# SCH-CAPE-Nucleo_Interface_V1R0.net
KiCad netlist of a schematic drawn in Altium Designer
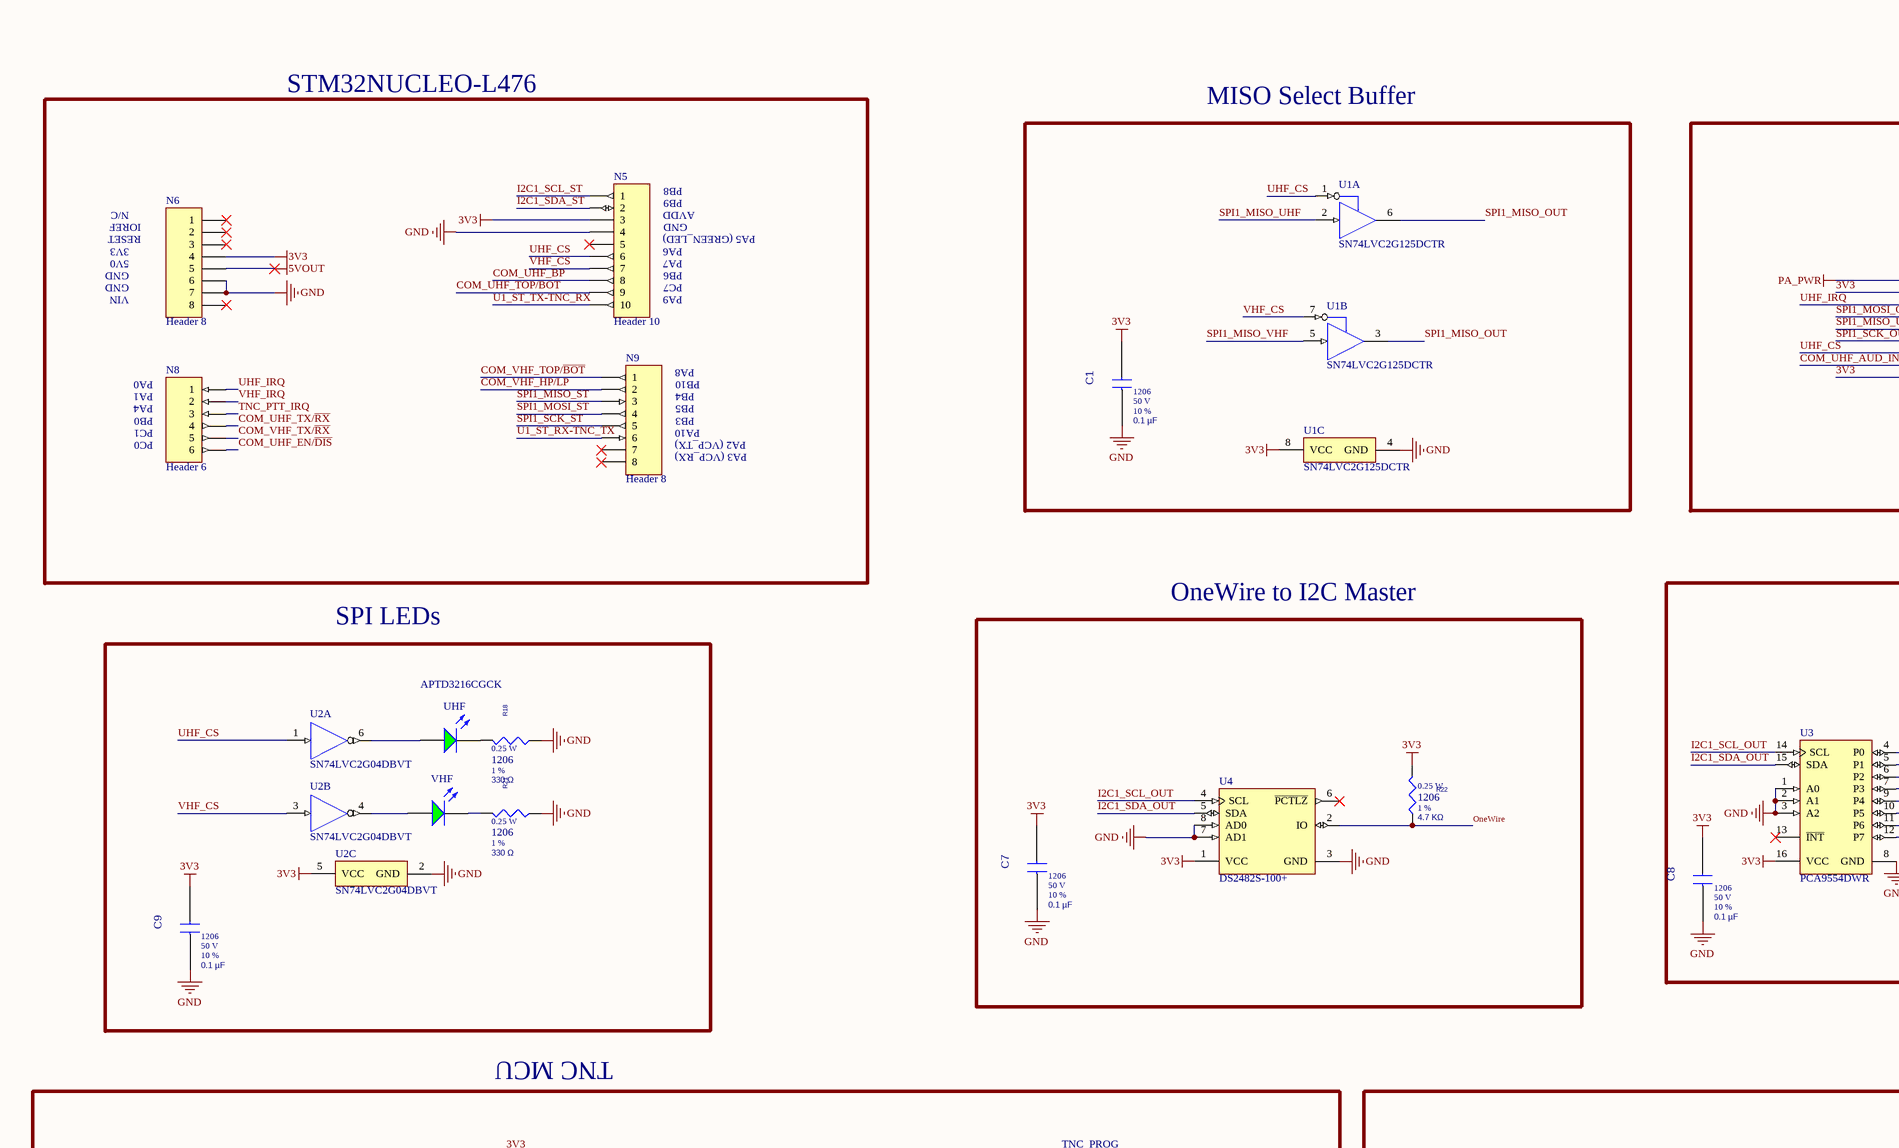
[diagram p0: SCH-CAPE-Nucleo_Interface_V1R0.SchDoc, top left]
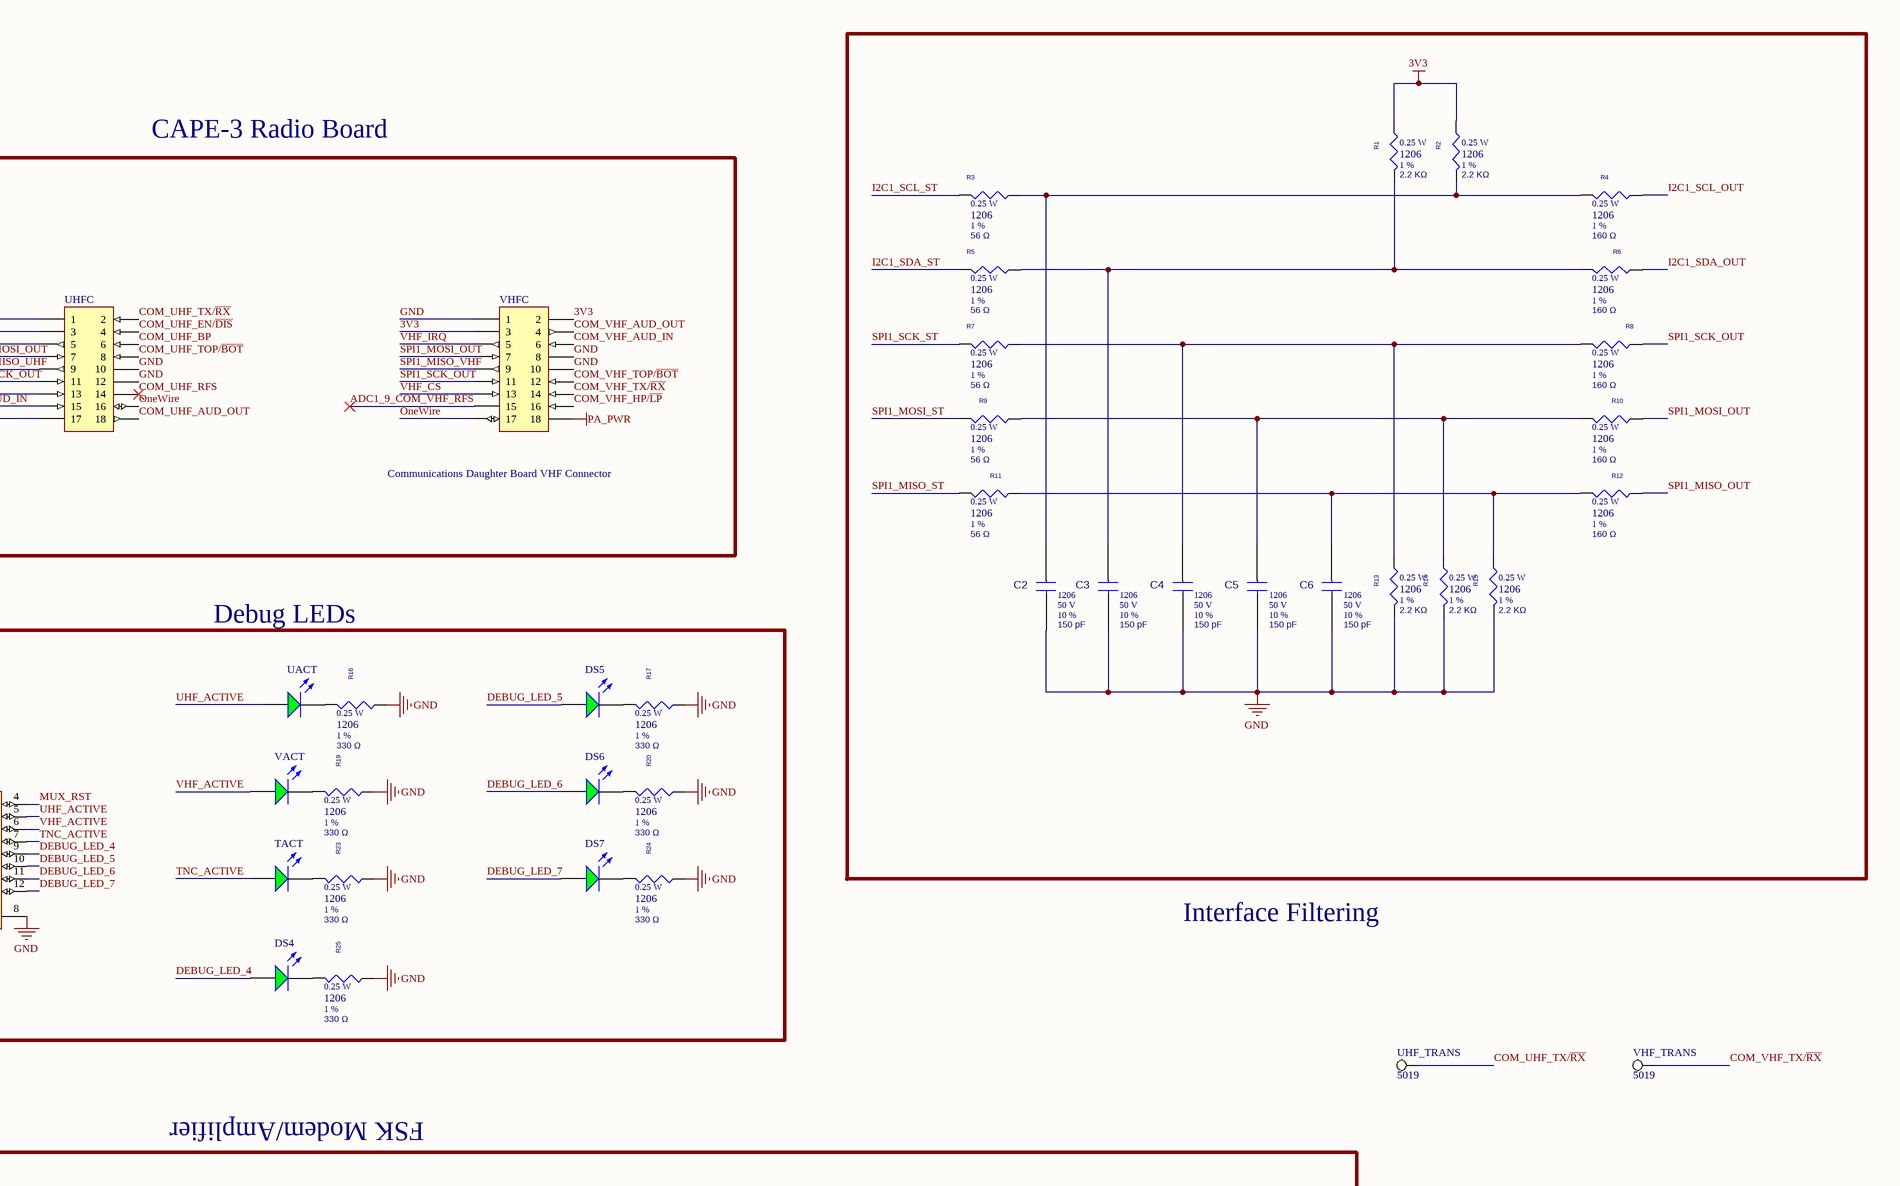
[diagram p1: SCH-CAPE-Nucleo_Interface_V1R0.SchDoc, top right]
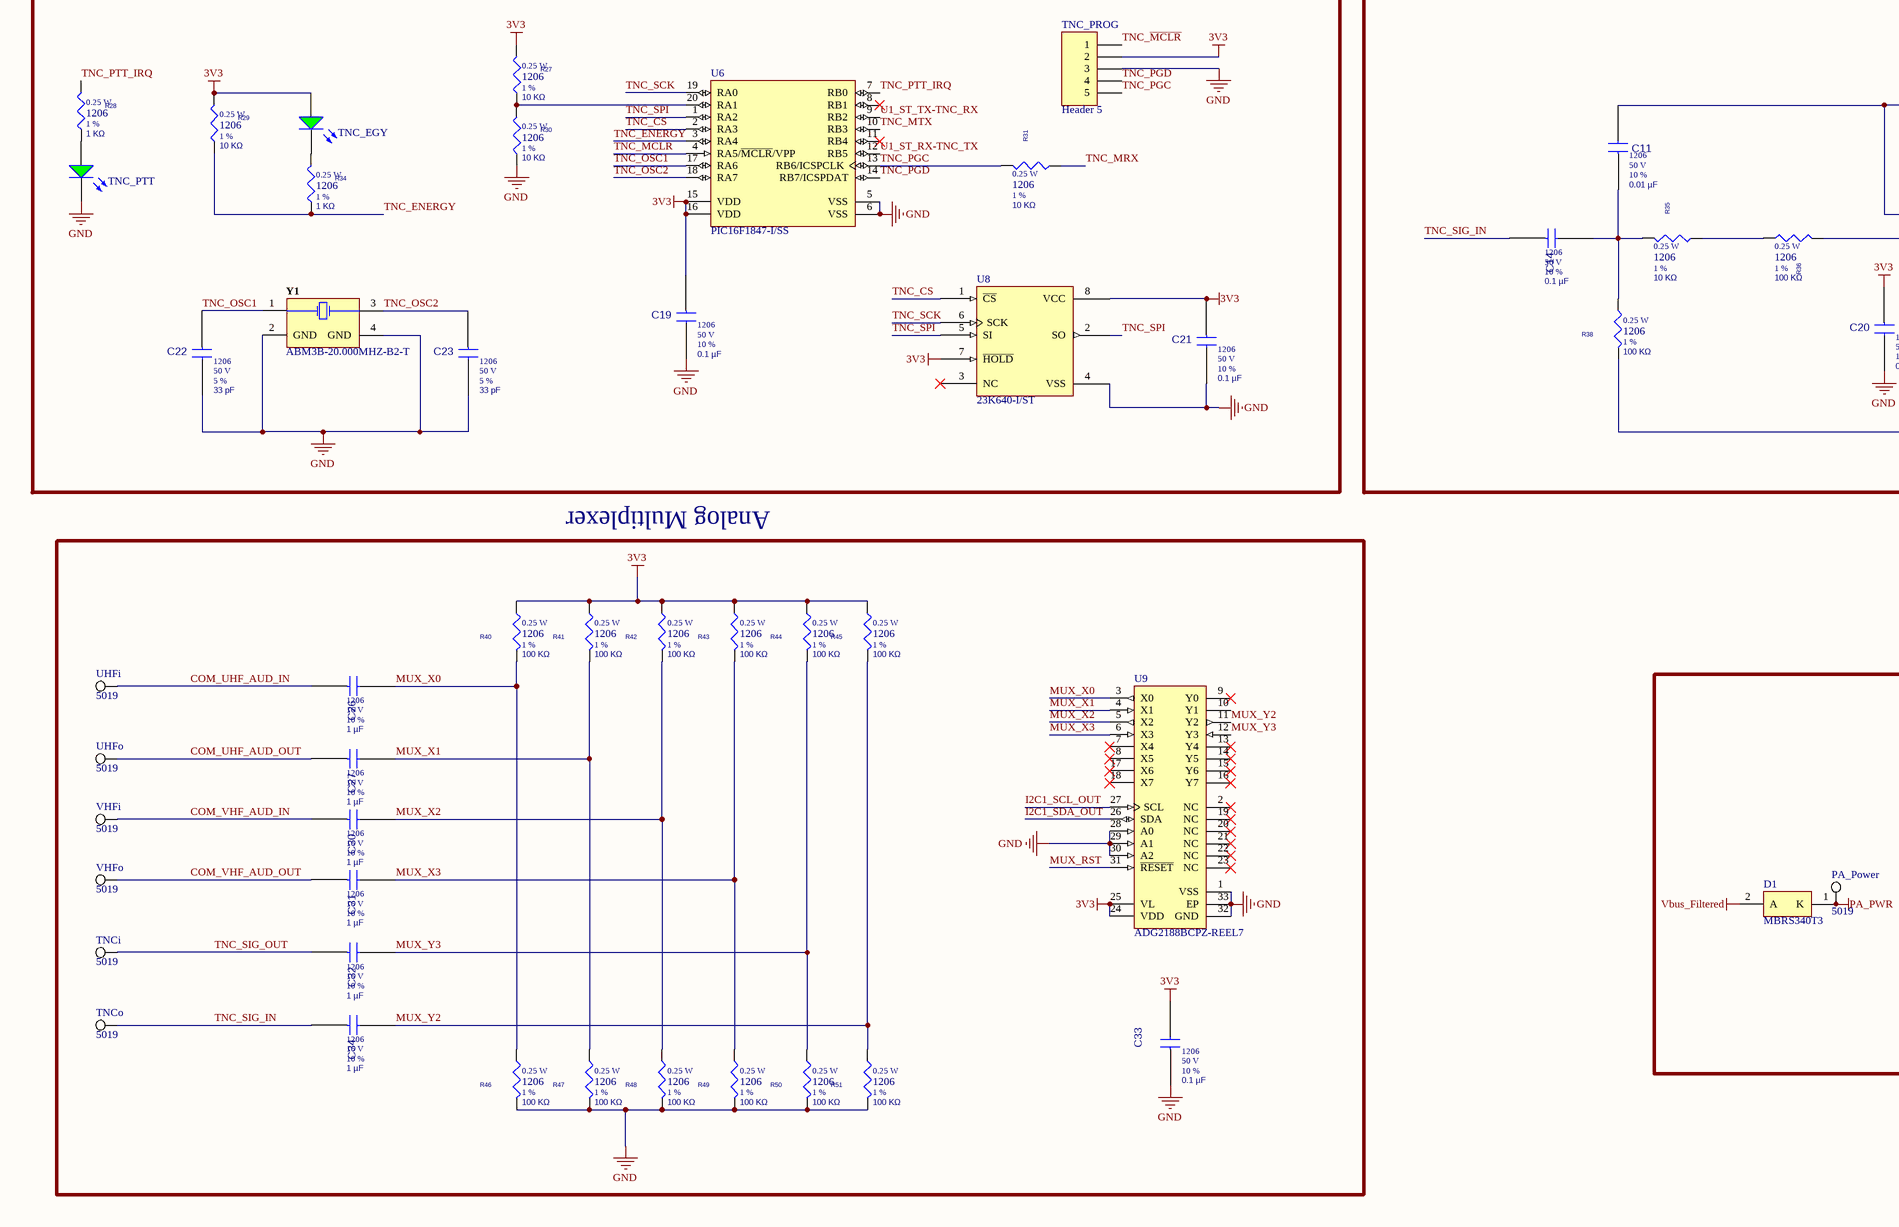
[diagram p2: SCH-CAPE-Nucleo_Interface_V1R0.SchDoc, bottom left]
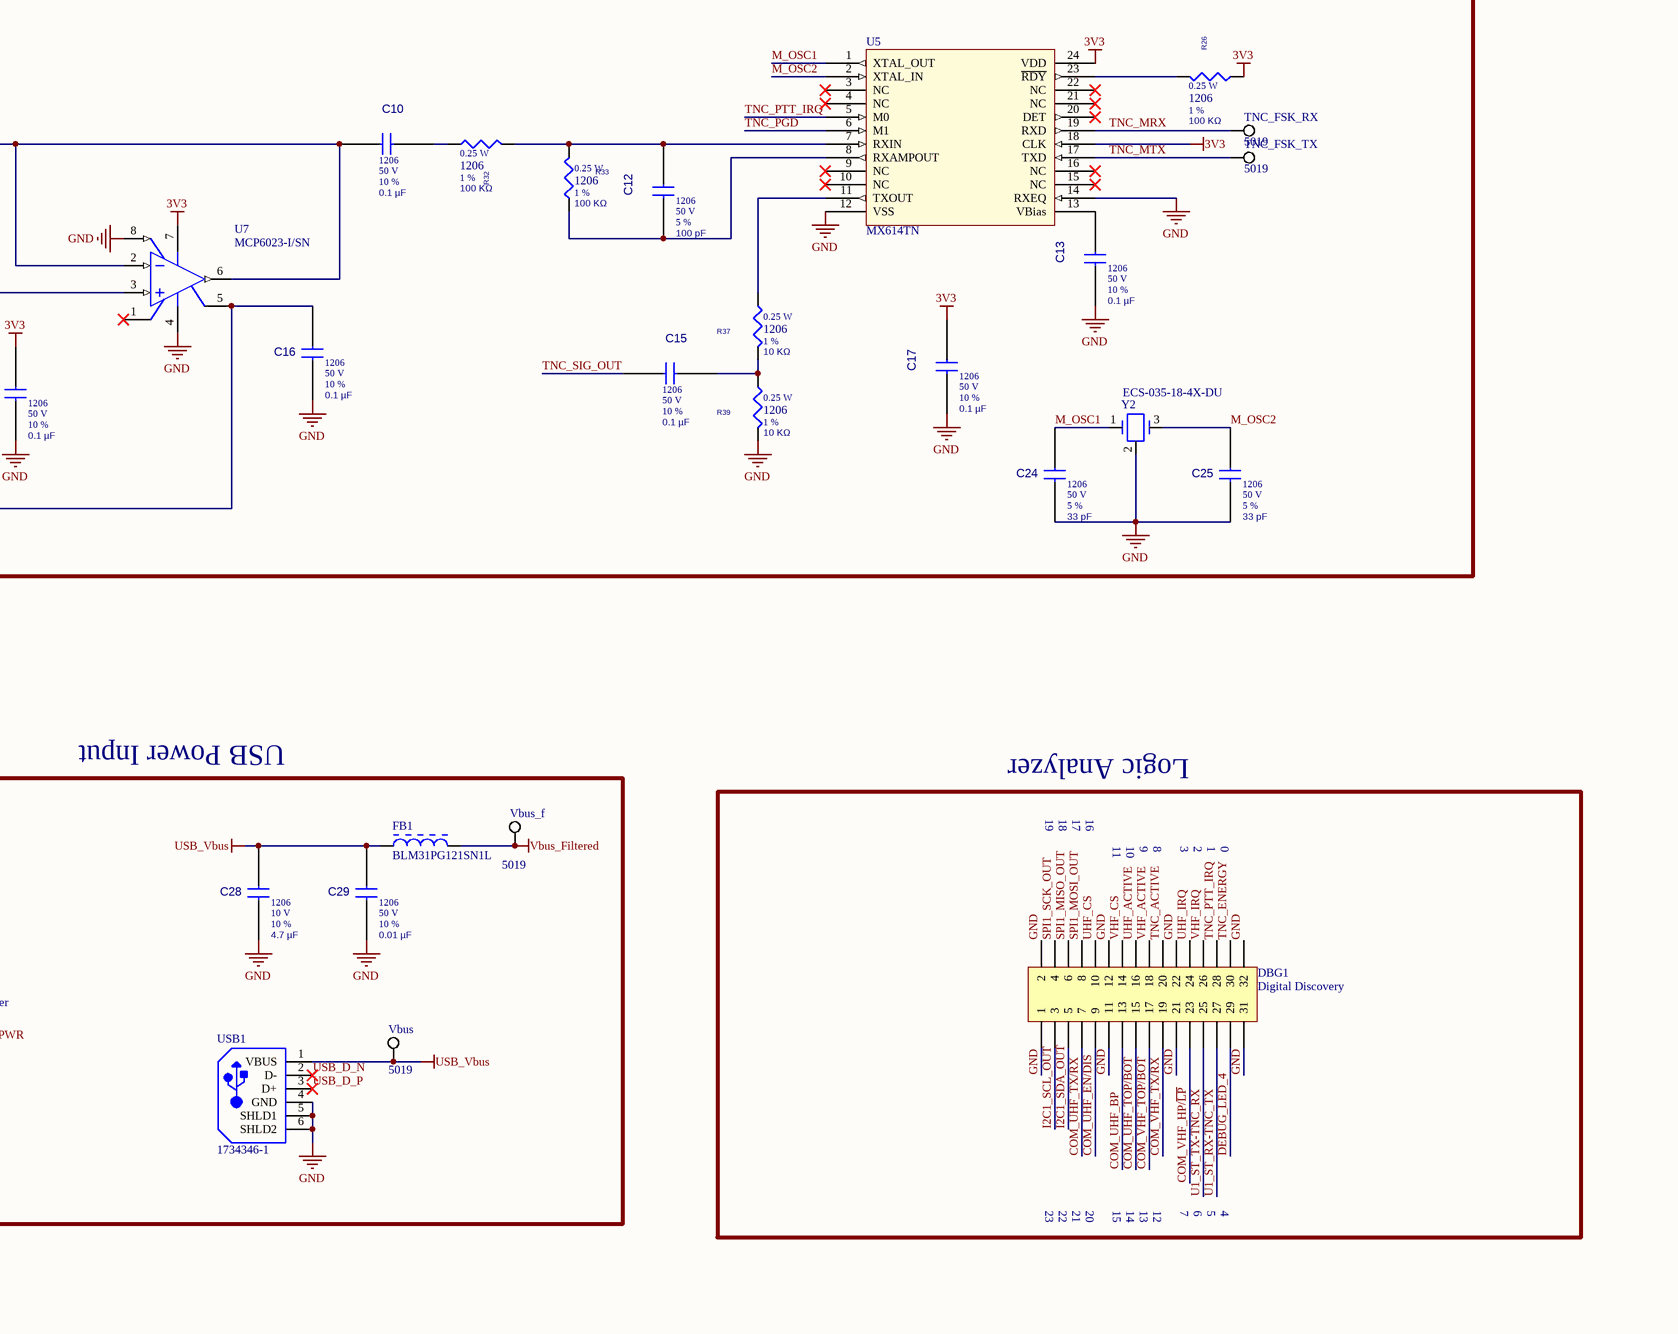
[diagram p3: SCH-CAPE-Nucleo_Interface_V1R0.SchDoc, bottom right]

(export (version "E")
  (design (tool "Eeschema 10.0.6"))
  (components
    (comp (ref "C1")
      (value "0.1 µF")
      (footprint "1206_GENERIC")
      (description "Ceramic Capacitor, =Value, =Tolerance, =VoltageRating, =Package")
      (fields
        (field (name "PART NUMBER") "CL31B104KBCNNNC")
        (field (name "MANUFACTURER") "Samsung")
        (field (name "PACKAGE") "1206")
        (field (name "VOLTAGE RATING") "50 V")
        (field (name "TOLERANCE") "10 %")
      )
      (libsource (lib "PEF") (part "SMT Capacitor"))
    )
    (comp (ref "C2")
      (value "150 pF")
      (footprint "1206_GENERIC")
      (description "Ceramic Capacitor, =Value, =Tolerance, =VoltageRating, =Package")
      (fields
        (field (name "PART NUMBER") "885012208101")
        (field (name "MANUFACTURER") "Wurth Electronics Inc.")
        (field (name "PACKAGE") "1206")
        (field (name "VOLTAGE RATING") "50 V")
        (field (name "TOLERANCE") "10 %")
      )
      (libsource (lib "PEF") (part "SMT Capacitor"))
    )
    (comp (ref "C3")
      (value "150 pF")
      (footprint "1206_GENERIC")
      (description "Ceramic Capacitor, =Value, =Tolerance, =VoltageRating, =Package")
      (fields
        (field (name "PART NUMBER") "885012208101")
        (field (name "MANUFACTURER") "Wurth Electronics Inc.")
        (field (name "PACKAGE") "1206")
        (field (name "VOLTAGE RATING") "50 V")
        (field (name "TOLERANCE") "10 %")
      )
      (libsource (lib "PEF") (part "SMT Capacitor"))
    )
    (comp (ref "C4")
      (value "150 pF")
      (footprint "1206_GENERIC")
      (description "Ceramic Capacitor, =Value, =Tolerance, =VoltageRating, =Package")
      (fields
        (field (name "PART NUMBER") "885012208101")
        (field (name "MANUFACTURER") "Wurth Electronics Inc.")
        (field (name "PACKAGE") "1206")
        (field (name "VOLTAGE RATING") "50 V")
        (field (name "TOLERANCE") "10 %")
      )
      (libsource (lib "PEF") (part "SMT Capacitor"))
    )
    (comp (ref "C5")
      (value "150 pF")
      (footprint "1206_GENERIC")
      (description "Ceramic Capacitor, =Value, =Tolerance, =VoltageRating, =Package")
      (fields
        (field (name "PART NUMBER") "885012208101")
        (field (name "MANUFACTURER") "Wurth Electronics Inc.")
        (field (name "PACKAGE") "1206")
        (field (name "VOLTAGE RATING") "50 V")
        (field (name "TOLERANCE") "10 %")
      )
      (libsource (lib "PEF") (part "SMT Capacitor"))
    )
    (comp (ref "C6")
      (value "150 pF")
      (footprint "1206_GENERIC")
      (description "Ceramic Capacitor, =Value, =Tolerance, =VoltageRating, =Package")
      (fields
        (field (name "PART NUMBER") "885012208101")
        (field (name "MANUFACTURER") "Wurth Electronics Inc.")
        (field (name "PACKAGE") "1206")
        (field (name "VOLTAGE RATING") "50 V")
        (field (name "TOLERANCE") "10 %")
      )
      (libsource (lib "PEF") (part "SMT Capacitor"))
    )
    (comp (ref "C7")
      (value "0.1 µF")
      (footprint "1206_GENERIC")
      (description "Ceramic Capacitor, =Value, =Tolerance, =VoltageRating, =Package")
      (fields
        (field (name "PART NUMBER") "CL31B104KBCNNNC")
        (field (name "MANUFACTURER") "Samsung")
        (field (name "PACKAGE") "1206")
        (field (name "VOLTAGE RATING") "50 V")
        (field (name "TOLERANCE") "10 %")
      )
      (libsource (lib "PEF") (part "SMT Capacitor"))
    )
    (comp (ref "C8")
      (value "0.1 µF")
      (footprint "1206_GENERIC")
      (description "Ceramic Capacitor, =Value, =Tolerance, =VoltageRating, =Package")
      (fields
        (field (name "PART NUMBER") "CL31B104KBCNNNC")
        (field (name "MANUFACTURER") "Samsung")
        (field (name "PACKAGE") "1206")
        (field (name "VOLTAGE RATING") "50 V")
        (field (name "TOLERANCE") "10 %")
      )
      (libsource (lib "PEF") (part "SMT Capacitor"))
    )
    (comp (ref "C9")
      (value "0.1 µF")
      (footprint "1206_GENERIC")
      (description "Ceramic Capacitor, =Value, =Tolerance, =VoltageRating, =Package")
      (fields
        (field (name "PART NUMBER") "CL31B104KBCNNNC")
        (field (name "MANUFACTURER") "Samsung")
        (field (name "PACKAGE") "1206")
        (field (name "VOLTAGE RATING") "50 V")
        (field (name "TOLERANCE") "10 %")
      )
      (libsource (lib "PEF") (part "SMT Capacitor"))
    )
    (comp (ref "C10")
      (value "0.1 µF")
      (footprint "1206_GENERIC")
      (description "Ceramic Capacitor, =Value, =Tolerance, =VoltageRating, =Package")
      (fields
        (field (name "PART NUMBER") "CL31B104KBCNNNC")
        (field (name "MANUFACTURER") "Samsung")
        (field (name "PACKAGE") "1206")
        (field (name "VOLTAGE RATING") "50 V")
        (field (name "TOLERANCE") "10 %")
      )
      (libsource (lib "PEF") (part "SMT Capacitor"))
    )
    (comp (ref "C11")
      (value "0.01 µF")
      (footprint "1206_GENERIC")
      (description "Ceramic Capacitor, =Value, =Tolerance, =VoltageRating, =Package")
      (fields
        (field (name "PART NUMBER") "CL31B103KBCNNNC")
        (field (name "MANUFACTURER") "Samsung")
        (field (name "PACKAGE") "1206")
        (field (name "VOLTAGE RATING") "50 V")
        (field (name "TOLERANCE") "10 %")
      )
      (libsource (lib "PEF") (part "SMT Capacitor"))
    )
    (comp (ref "C12")
      (value "100 pF")
      (footprint "1206_GENERIC")
      (description "Ceramic Capacitor, =Value, =Tolerance, =VoltageRating, =Package")
      (fields
        (field (name "PART NUMBER") "CL31C101JBCNNNC")
        (field (name "MANUFACTURER") "Samsung")
        (field (name "PACKAGE") "1206")
        (field (name "VOLTAGE RATING") "50 V")
        (field (name "TOLERANCE") "5 %")
      )
      (libsource (lib "PEF") (part "SMT Capacitor"))
    )
    (comp (ref "C13")
      (value "0.1 µF")
      (footprint "1206_GENERIC")
      (description "Ceramic Capacitor, =Value, =Tolerance, =VoltageRating, =Package")
      (fields
        (field (name "PART NUMBER") "CL31B104KBCNNNC")
        (field (name "MANUFACTURER") "Samsung")
        (field (name "PACKAGE") "1206")
        (field (name "VOLTAGE RATING") "50 V")
        (field (name "TOLERANCE") "10 %")
      )
      (libsource (lib "PEF") (part "SMT Capacitor"))
    )
    (comp (ref "C14")
      (value "0.1 µF")
      (footprint "1206_GENERIC")
      (description "Ceramic Capacitor, =Value, =Tolerance, =VoltageRating, =Package")
      (fields
        (field (name "PART NUMBER") "CL31B104KBCNNNC")
        (field (name "MANUFACTURER") "Samsung")
        (field (name "PACKAGE") "1206")
        (field (name "VOLTAGE RATING") "50 V")
        (field (name "TOLERANCE") "10 %")
      )
      (libsource (lib "PEF") (part "SMT Capacitor"))
    )
    (comp (ref "C15")
      (value "0.1 µF")
      (footprint "1206_GENERIC")
      (description "Ceramic Capacitor, =Value, =Tolerance, =VoltageRating, =Package")
      (fields
        (field (name "PART NUMBER") "CL31B104KBCNNNC")
        (field (name "MANUFACTURER") "Samsung")
        (field (name "PACKAGE") "1206")
        (field (name "VOLTAGE RATING") "50 V")
        (field (name "TOLERANCE") "10 %")
      )
      (libsource (lib "PEF") (part "SMT Capacitor"))
    )
    (comp (ref "C16")
      (value "0.1 µF")
      (footprint "1206_GENERIC")
      (description "Ceramic Capacitor, =Value, =Tolerance, =VoltageRating, =Package")
      (fields
        (field (name "PART NUMBER") "CL31B104KBCNNNC")
        (field (name "MANUFACTURER") "Samsung")
        (field (name "PACKAGE") "1206")
        (field (name "VOLTAGE RATING") "50 V")
        (field (name "TOLERANCE") "10 %")
      )
      (libsource (lib "PEF") (part "SMT Capacitor"))
    )
    (comp (ref "C17")
      (value "0.1 µF")
      (footprint "1206_GENERIC")
      (description "Ceramic Capacitor, =Value, =Tolerance, =VoltageRating, =Package")
      (fields
        (field (name "PART NUMBER") "CL31B104KBCNNNC")
        (field (name "MANUFACTURER") "Samsung")
        (field (name "PACKAGE") "1206")
        (field (name "VOLTAGE RATING") "50 V")
        (field (name "TOLERANCE") "10 %")
      )
      (libsource (lib "PEF") (part "SMT Capacitor"))
    )
    (comp (ref "C19")
      (value "0.1 µF")
      (footprint "1206_GENERIC")
      (description "Ceramic Capacitor, =Value, =Tolerance, =VoltageRating, =Package")
      (fields
        (field (name "PART NUMBER") "CL31B104KBCNNNC")
        (field (name "MANUFACTURER") "Samsung")
        (field (name "PACKAGE") "1206")
        (field (name "VOLTAGE RATING") "50 V")
        (field (name "TOLERANCE") "10 %")
      )
      (libsource (lib "PEF") (part "SMT Capacitor"))
    )
    (comp (ref "C20")
      (value "0.1 µF")
      (footprint "1206_GENERIC")
      (description "Ceramic Capacitor, =Value, =Tolerance, =VoltageRating, =Package")
      (fields
        (field (name "PART NUMBER") "CL31B104KBCNNNC")
        (field (name "MANUFACTURER") "Samsung")
        (field (name "PACKAGE") "1206")
        (field (name "VOLTAGE RATING") "50 V")
        (field (name "TOLERANCE") "10 %")
      )
      (libsource (lib "PEF") (part "SMT Capacitor"))
    )
    (comp (ref "C21")
      (value "0.1 µF")
      (footprint "1206_GENERIC")
      (description "Ceramic Capacitor, =Value, =Tolerance, =VoltageRating, =Package")
      (fields
        (field (name "PART NUMBER") "CL31B104KBCNNNC")
        (field (name "MANUFACTURER") "Samsung")
        (field (name "PACKAGE") "1206")
        (field (name "VOLTAGE RATING") "50 V")
        (field (name "TOLERANCE") "10 %")
      )
      (libsource (lib "PEF") (part "SMT Capacitor"))
    )
    (comp (ref "C22")
      (value "33 pF")
      (footprint "1206_GENERIC")
      (description "Ceramic Capacitor, =Value, =Tolerance, =VoltageRating, =Package")
      (fields
        (field (name "PART NUMBER") "CL31C330JBCNNNC")
        (field (name "MANUFACTURER") "Samsung")
        (field (name "PACKAGE") "1206")
        (field (name "VOLTAGE RATING") "50 V")
        (field (name "TOLERANCE") "5 %")
      )
      (libsource (lib "PEF") (part "SMT Capacitor"))
    )
    (comp (ref "C23")
      (value "33 pF")
      (footprint "1206_GENERIC")
      (description "Ceramic Capacitor, =Value, =Tolerance, =VoltageRating, =Package")
      (fields
        (field (name "PART NUMBER") "CL31C330JBCNNNC")
        (field (name "MANUFACTURER") "Samsung")
        (field (name "PACKAGE") "1206")
        (field (name "VOLTAGE RATING") "50 V")
        (field (name "TOLERANCE") "5 %")
      )
      (libsource (lib "PEF") (part "SMT Capacitor"))
    )
    (comp (ref "C24")
      (value "33 pF")
      (footprint "1206_GENERIC")
      (description "Ceramic Capacitor, =Value, =Tolerance, =VoltageRating, =Package")
      (fields
        (field (name "PART NUMBER") "CL31C330JBCNNNC")
        (field (name "MANUFACTURER") "Samsung")
        (field (name "PACKAGE") "1206")
        (field (name "VOLTAGE RATING") "50 V")
        (field (name "TOLERANCE") "5 %")
      )
      (libsource (lib "PEF") (part "SMT Capacitor"))
    )
    (comp (ref "C25")
      (value "33 pF")
      (footprint "1206_GENERIC")
      (description "Ceramic Capacitor, =Value, =Tolerance, =VoltageRating, =Package")
      (fields
        (field (name "PART NUMBER") "CL31C330JBCNNNC")
        (field (name "MANUFACTURER") "Samsung")
        (field (name "PACKAGE") "1206")
        (field (name "VOLTAGE RATING") "50 V")
        (field (name "TOLERANCE") "5 %")
      )
      (libsource (lib "PEF") (part "SMT Capacitor"))
    )
    (comp (ref "C26")
      (value "1 µF")
      (footprint "1206_GENERIC")
      (description "Ceramic Capacitor, =Value, =Tolerance, =VoltageRating, =Package")
      (fields
        (field (name "PART NUMBER") "CL31B105KOFNNNE")
        (field (name "MANUFACTURER") "Samsung")
        (field (name "PACKAGE") "1206")
        (field (name "VOLTAGE RATING") "16 V")
        (field (name "TOLERANCE") "10 %")
      )
      (libsource (lib "PEF") (part "SMT Capacitor"))
    )
    (comp (ref "C27")
      (value "1 µF")
      (footprint "1206_GENERIC")
      (description "Ceramic Capacitor, =Value, =Tolerance, =VoltageRating, =Package")
      (fields
        (field (name "PART NUMBER") "CL31B105KOFNNNE")
        (field (name "MANUFACTURER") "Samsung")
        (field (name "PACKAGE") "1206")
        (field (name "VOLTAGE RATING") "16 V")
        (field (name "TOLERANCE") "10 %")
      )
      (libsource (lib "PEF") (part "SMT Capacitor"))
    )
    (comp (ref "C28")
      (value "4.7 µF")
      (footprint "1206_GENERIC")
      (description "Ceramic Capacitor, =Value, =Tolerance, =VoltageRating, =Package")
      (fields
        (field (name "PART NUMBER") "CL31A475KPHNNNE")
        (field (name "MANUFACTURER") "Samsung")
        (field (name "PACKAGE") "1206")
        (field (name "VOLTAGE RATING") "10 V")
        (field (name "TOLERANCE") "10 %")
      )
      (libsource (lib "PEF") (part "SMT Capacitor"))
    )
    (comp (ref "C29")
      (value "0.01 µF")
      (footprint "1206_GENERIC")
      (description "Ceramic Capacitor, =Value, =Tolerance, =VoltageRating, =Package")
      (fields
        (field (name "PART NUMBER") "CL31B103KBCNNNC")
        (field (name "MANUFACTURER") "Samsung")
        (field (name "PACKAGE") "1206")
        (field (name "VOLTAGE RATING") "50 V")
        (field (name "TOLERANCE") "10 %")
      )
      (libsource (lib "PEF") (part "SMT Capacitor"))
    )
    (comp (ref "C30")
      (value "1 µF")
      (footprint "1206_GENERIC")
      (description "Ceramic Capacitor, =Value, =Tolerance, =VoltageRating, =Package")
      (fields
        (field (name "PART NUMBER") "CL31B105KOFNNNE")
        (field (name "MANUFACTURER") "Samsung")
        (field (name "PACKAGE") "1206")
        (field (name "VOLTAGE RATING") "16 V")
        (field (name "TOLERANCE") "10 %")
      )
      (libsource (lib "PEF") (part "SMT Capacitor"))
    )
    (comp (ref "C31")
      (value "1 µF")
      (footprint "1206_GENERIC")
      (description "Ceramic Capacitor, =Value, =Tolerance, =VoltageRating, =Package")
      (fields
        (field (name "PART NUMBER") "CL31B105KOFNNNE")
        (field (name "MANUFACTURER") "Samsung")
        (field (name "PACKAGE") "1206")
        (field (name "VOLTAGE RATING") "16 V")
        (field (name "TOLERANCE") "10 %")
      )
      (libsource (lib "PEF") (part "SMT Capacitor"))
    )
    (comp (ref "C32")
      (value "1 µF")
      (footprint "1206_GENERIC")
      (description "Ceramic Capacitor, =Value, =Tolerance, =VoltageRating, =Package")
      (fields
        (field (name "PART NUMBER") "CL31B105KOFNNNE")
        (field (name "MANUFACTURER") "Samsung")
        (field (name "PACKAGE") "1206")
        (field (name "VOLTAGE RATING") "16 V")
        (field (name "TOLERANCE") "10 %")
      )
      (libsource (lib "PEF") (part "SMT Capacitor"))
    )
    (comp (ref "C33")
      (value "0.1 µF")
      (footprint "1206_GENERIC")
      (description "Ceramic Capacitor, =Value, =Tolerance, =VoltageRating, =Package")
      (fields
        (field (name "PART NUMBER") "CL31B104KBCNNNC")
        (field (name "MANUFACTURER") "Samsung")
        (field (name "PACKAGE") "1206")
        (field (name "VOLTAGE RATING") "50 V")
        (field (name "TOLERANCE") "10 %")
      )
      (libsource (lib "PEF") (part "SMT Capacitor"))
    )
    (comp (ref "C34")
      (value "1 µF")
      (footprint "1206_GENERIC")
      (description "Ceramic Capacitor, =Value, =Tolerance, =VoltageRating, =Package")
      (fields
        (field (name "PART NUMBER") "CL31B105KOFNNNE")
        (field (name "MANUFACTURER") "Samsung")
        (field (name "PACKAGE") "1206")
        (field (name "VOLTAGE RATING") "16 V")
        (field (name "TOLERANCE") "10 %")
      )
      (libsource (lib "PEF") (part "SMT Capacitor"))
    )
    (comp (ref "D1")
      (value "MBRS340T3")
      (footprint "ONSC-SMC-2-403-03_V")
      (description "Schottky Power Rectifier, 2-Pin SMC, Tape and Reel")
      (fields (field (name "MANUFACTURER") "On Semiconductor"))
      (libsource (lib "Altium Content Vault") (part "ONSC-D-K1A2-2_A"))
    )
    (comp (ref "DBG1")
      (value "Digital Discovery")
      (footprint "HDR2X16H")
      (description "Header, 16-Pin, Dual row, Right Angle")
      (fields
        (field (name "PART NUMBER") "SSQ-116-02-T-D-RA")
        (field (name "MANUFACTURER") "Samtec")
        (field (name "PUBLISHER") "Altium Limited")
      )
      (libsource (lib "Miscellaneous Connectors") (part "Header 16X2H"))
    )
    (comp (ref "DS4")
      (value "APTD3216CGCK")
      (footprint "KING-APTD3216CGCK_V")
      (description "Chip LED Lamp, Green, 5 V, 30 mA, -40 to 85 degC, 2-Pin SMD, RoHS, Tape and Reel")
      (fields (field (name "MANUFACTURER") "Kingbright"))
      (libsource (lib "Altium Content Vault") (part "LED-GREEN-AK-2"))
    )
    (comp (ref "DS5")
      (value "APTD3216CGCK")
      (footprint "KING-APTD3216CGCK_V")
      (description "Chip LED Lamp, Green, 5 V, 30 mA, -40 to 85 degC, 2-Pin SMD, RoHS, Tape and Reel")
      (fields (field (name "MANUFACTURER") "Kingbright"))
      (libsource (lib "Altium Content Vault") (part "LED-GREEN-AK-2"))
    )
    (comp (ref "DS6")
      (value "APTD3216CGCK")
      (footprint "KING-APTD3216CGCK_V")
      (description "Chip LED Lamp, Green, 5 V, 30 mA, -40 to 85 degC, 2-Pin SMD, RoHS, Tape and Reel")
      (fields (field (name "MANUFACTURER") "Kingbright"))
      (libsource (lib "Altium Content Vault") (part "LED-GREEN-AK-2"))
    )
    (comp (ref "DS7")
      (value "APTD3216CGCK")
      (footprint "KING-APTD3216CGCK_V")
      (description "Chip LED Lamp, Green, 5 V, 30 mA, -40 to 85 degC, 2-Pin SMD, RoHS, Tape and Reel")
      (fields (field (name "MANUFACTURER") "Kingbright"))
      (libsource (lib "Altium Content Vault") (part "LED-GREEN-AK-2"))
    )
    (comp (ref "FB1")
      (value "BLM31PG121SN1L")
      (footprint "MURA-BLM31-B35-CHIP-2_V2")
      (fields (field (name "MANUFACTURER") "Murata"))
      (libsource (lib "Altium Content Vault") (part "MURA-FB-2"))
    )
    (comp (ref "N5")
      (value "Header 10")
      (footprint "HDR1X10")
      (description "Header, 10-Pin")
      (fields (field (name "PUBLISHER") "Altium Limited"))
      (libsource (lib "Miscellaneous Connectors") (part "Header 10"))
    )
    (comp (ref "N6")
      (value "Header 8")
      (footprint "HDR1X8")
      (description "Header, 8-Pin")
      (fields (field (name "PUBLISHER") "Altium Limited"))
      (libsource (lib "Miscellaneous Connectors") (part "Header 8"))
    )
    (comp (ref "N8")
      (value "Header 6")
      (footprint "HDR1X6")
      (description "Header, 6-Pin")
      (fields (field (name "PUBLISHER") "Altium Limited"))
      (libsource (lib "Miscellaneous Connectors") (part "Header 6"))
    )
    (comp (ref "N9")
      (value "Header 8")
      (footprint "HDR1X8")
      (description "Header, 8-Pin")
      (fields (field (name "PUBLISHER") "Altium Limited"))
      (libsource (lib "") (part "Header 8_1"))
    )
    (comp (ref "PA_Power")
      (value "5019")
      (footprint "KSTN-5019_V")
      (description "Test Point, 1 Position SMD, RoHS, Tape and Reel")
      (fields (field (name "MANUFACTURER") "Keystone Electronics"))
      (libsource (lib "Altium Content Vault") (part "TESTPOINT_WHITE"))
    )
    (comp (ref "R1")
      (value "2.2 KΩ")
      (footprint "1206_GENERIC")
      (description "Generic SMT Resistor")
      (fields
        (field (name "PART NUMBER") "RC1206FR-072K2L")
        (field (name "MANUFACTURER") "Yageo")
        (field (name "POWER RATING") "0.25 W")
        (field (name "PACKAGE") "1206")
        (field (name "TOLERANCE") "1 %")
      )
      (libsource (lib "PEF") (part "SMT Resistor"))
    )
    (comp (ref "R2")
      (value "2.2 KΩ")
      (footprint "1206_GENERIC")
      (description "Generic SMT Resistor")
      (fields
        (field (name "PART NUMBER") "RC1206FR-072K2L")
        (field (name "MANUFACTURER") "Yageo")
        (field (name "POWER RATING") "0.25 W")
        (field (name "PACKAGE") "1206")
        (field (name "TOLERANCE") "1 %")
      )
      (libsource (lib "PEF") (part "SMT Resistor"))
    )
    (comp (ref "R3")
      (value "56 Ω")
      (footprint "1206_GENERIC")
      (description "Generic SMT Resistor")
      (fields
        (field (name "PART NUMBER") "RC1206FR-0756RL")
        (field (name "MANUFACTURER") "Yageo")
        (field (name "POWER RATING") "0.25 W")
        (field (name "PACKAGE") "1206")
        (field (name "TOLERANCE") "1 %")
      )
      (libsource (lib "PEF") (part "SMT Resistor"))
    )
    (comp (ref "R4")
      (value "160 Ω")
      (footprint "1206_GENERIC")
      (description "Generic SMT Resistor")
      (fields
        (field (name "PART NUMBER") "RC1206FR-07160RL")
        (field (name "MANUFACTURER") "Yageo")
        (field (name "POWER RATING") "0.25 W")
        (field (name "PACKAGE") "1206")
        (field (name "TOLERANCE") "1 %")
      )
      (libsource (lib "PEF") (part "SMT Resistor"))
    )
    (comp (ref "R5")
      (value "56 Ω")
      (footprint "1206_GENERIC")
      (description "Generic SMT Resistor")
      (fields
        (field (name "PART NUMBER") "RC1206FR-0756RL")
        (field (name "MANUFACTURER") "Yageo")
        (field (name "POWER RATING") "0.25 W")
        (field (name "PACKAGE") "1206")
        (field (name "TOLERANCE") "1 %")
      )
      (libsource (lib "PEF") (part "SMT Resistor"))
    )
    (comp (ref "R6")
      (value "160 Ω")
      (footprint "1206_GENERIC")
      (description "Generic SMT Resistor")
      (fields
        (field (name "PART NUMBER") "RC1206FR-07160RL")
        (field (name "MANUFACTURER") "Yageo")
        (field (name "POWER RATING") "0.25 W")
        (field (name "PACKAGE") "1206")
        (field (name "TOLERANCE") "1 %")
      )
      (libsource (lib "PEF") (part "SMT Resistor"))
    )
    (comp (ref "R7")
      (value "56 Ω")
      (footprint "1206_GENERIC")
      (description "Generic SMT Resistor")
      (fields
        (field (name "PART NUMBER") "RC1206FR-0756RL")
        (field (name "MANUFACTURER") "Yageo")
        (field (name "POWER RATING") "0.25 W")
        (field (name "PACKAGE") "1206")
        (field (name "TOLERANCE") "1 %")
      )
      (libsource (lib "PEF") (part "SMT Resistor"))
    )
    (comp (ref "R8")
      (value "160 Ω")
      (footprint "1206_GENERIC")
      (description "Generic SMT Resistor")
      (fields
        (field (name "PART NUMBER") "RC1206FR-07160RL")
        (field (name "MANUFACTURER") "Yageo")
        (field (name "POWER RATING") "0.25 W")
        (field (name "PACKAGE") "1206")
        (field (name "TOLERANCE") "1 %")
      )
      (libsource (lib "PEF") (part "SMT Resistor"))
    )
    (comp (ref "R9")
      (value "56 Ω")
      (footprint "1206_GENERIC")
      (description "Generic SMT Resistor")
      (fields
        (field (name "PART NUMBER") "RC1206FR-0756RL")
        (field (name "MANUFACTURER") "Yageo")
        (field (name "POWER RATING") "0.25 W")
        (field (name "PACKAGE") "1206")
        (field (name "TOLERANCE") "1 %")
      )
      (libsource (lib "PEF") (part "SMT Resistor"))
    )
    (comp (ref "R10")
      (value "160 Ω")
      (footprint "1206_GENERIC")
      (description "Generic SMT Resistor")
      (fields
        (field (name "PART NUMBER") "RC1206FR-07160RL")
        (field (name "MANUFACTURER") "Yageo")
        (field (name "POWER RATING") "0.25 W")
        (field (name "PACKAGE") "1206")
        (field (name "TOLERANCE") "1 %")
      )
      (libsource (lib "PEF") (part "SMT Resistor"))
    )
    (comp (ref "R11")
      (value "56 Ω")
      (footprint "1206_GENERIC")
      (description "Generic SMT Resistor")
      (fields
        (field (name "PART NUMBER") "RC1206FR-0756RL")
        (field (name "MANUFACTURER") "Yageo")
        (field (name "POWER RATING") "0.25 W")
        (field (name "PACKAGE") "1206")
        (field (name "TOLERANCE") "1 %")
      )
      (libsource (lib "PEF") (part "SMT Resistor"))
    )
    (comp (ref "R12")
      (value "160 Ω")
      (footprint "1206_GENERIC")
      (description "Generic SMT Resistor")
      (fields
        (field (name "PART NUMBER") "RC1206FR-07160RL")
        (field (name "MANUFACTURER") "Yageo")
        (field (name "POWER RATING") "0.25 W")
        (field (name "PACKAGE") "1206")
        (field (name "TOLERANCE") "1 %")
      )
      (libsource (lib "PEF") (part "SMT Resistor"))
    )
    (comp (ref "R13")
      (value "2.2 KΩ")
      (footprint "1206_GENERIC")
      (description "Generic SMT Resistor")
      (fields
        (field (name "PART NUMBER") "RC1206FR-072K2L")
        (field (name "MANUFACTURER") "Yageo")
        (field (name "POWER RATING") "0.25 W")
        (field (name "PACKAGE") "1206")
        (field (name "TOLERANCE") "1 %")
      )
      (libsource (lib "PEF") (part "SMT Resistor"))
    )
    (comp (ref "R14")
      (value "2.2 KΩ")
      (footprint "1206_GENERIC")
      (description "Generic SMT Resistor")
      (fields
        (field (name "PART NUMBER") "RC1206FR-072K2L")
        (field (name "MANUFACTURER") "Yageo")
        (field (name "POWER RATING") "0.25 W")
        (field (name "PACKAGE") "1206")
        (field (name "TOLERANCE") "1 %")
      )
      (libsource (lib "PEF") (part "SMT Resistor"))
    )
    (comp (ref "R15")
      (value "2.2 KΩ")
      (footprint "1206_GENERIC")
      (description "Generic SMT Resistor")
      (fields
        (field (name "PART NUMBER") "RC1206FR-072K2L")
        (field (name "MANUFACTURER") "Yageo")
        (field (name "POWER RATING") "0.25 W")
        (field (name "PACKAGE") "1206")
        (field (name "TOLERANCE") "1 %")
      )
      (libsource (lib "PEF") (part "SMT Resistor"))
    )
    (comp (ref "R16")
      (value "330 Ω")
      (footprint "1206_GENERIC")
      (description "Generic SMT Resistor")
      (fields
        (field (name "PART NUMBER") "RC1206FR-07330RL")
        (field (name "MANUFACTURER") "Yageo")
        (field (name "POWER RATING") "0.25 W")
        (field (name "PACKAGE") "1206")
        (field (name "TOLERANCE") "1 %")
      )
      (libsource (lib "PEF") (part "SMT Resistor"))
    )
    (comp (ref "R17")
      (value "330 Ω")
      (footprint "1206_GENERIC")
      (description "Generic SMT Resistor")
      (fields
        (field (name "PART NUMBER") "RC1206FR-07330RL")
        (field (name "MANUFACTURER") "Yageo")
        (field (name "POWER RATING") "0.25 W")
        (field (name "PACKAGE") "1206")
        (field (name "TOLERANCE") "1 %")
      )
      (libsource (lib "PEF") (part "SMT Resistor"))
    )
    (comp (ref "R18")
      (value "330 Ω")
      (footprint "1206_GENERIC")
      (description "Generic SMT Resistor")
      (fields
        (field (name "PART NUMBER") "RC1206FR-07330RL")
        (field (name "MANUFACTURER") "Yageo")
        (field (name "POWER RATING") "0.25 W")
        (field (name "PACKAGE") "1206")
        (field (name "TOLERANCE") "1 %")
      )
      (libsource (lib "PEF") (part "SMT Resistor"))
    )
    (comp (ref "R19")
      (value "330 Ω")
      (footprint "1206_GENERIC")
      (description "Generic SMT Resistor")
      (fields
        (field (name "PART NUMBER") "RC1206FR-07330RL")
        (field (name "MANUFACTURER") "Yageo")
        (field (name "POWER RATING") "0.25 W")
        (field (name "PACKAGE") "1206")
        (field (name "TOLERANCE") "1 %")
      )
      (libsource (lib "PEF") (part "SMT Resistor"))
    )
    (comp (ref "R20")
      (value "330 Ω")
      (footprint "1206_GENERIC")
      (description "Generic SMT Resistor")
      (fields
        (field (name "PART NUMBER") "RC1206FR-07330RL")
        (field (name "MANUFACTURER") "Yageo")
        (field (name "POWER RATING") "0.25 W")
        (field (name "PACKAGE") "1206")
        (field (name "TOLERANCE") "1 %")
      )
      (libsource (lib "PEF") (part "SMT Resistor"))
    )
    (comp (ref "R21")
      (value "330 Ω")
      (footprint "1206_GENERIC")
      (description "Generic SMT Resistor")
      (fields
        (field (name "PART NUMBER") "RC1206FR-07330RL")
        (field (name "MANUFACTURER") "Yageo")
        (field (name "POWER RATING") "0.25 W")
        (field (name "PACKAGE") "1206")
        (field (name "TOLERANCE") "1 %")
      )
      (libsource (lib "PEF") (part "SMT Resistor"))
    )
    (comp (ref "R22")
      (value "4.7 KΩ")
      (footprint "1206_GENERIC")
      (description "Generic SMT Resistor")
      (fields
        (field (name "PART NUMBER") "RC1206FR-074K7L")
        (field (name "MANUFACTURER") "Yageo")
        (field (name "POWER RATING") "0.25 W")
        (field (name "PACKAGE") "1206")
        (field (name "TOLERANCE") "1 %")
      )
      (libsource (lib "PEF") (part "SMT Resistor"))
    )
    (comp (ref "R23")
      (value "330 Ω")
      (footprint "1206_GENERIC")
      (description "Generic SMT Resistor")
      (fields
        (field (name "PART NUMBER") "RC1206FR-07330RL")
        (field (name "MANUFACTURER") "Yageo")
        (field (name "POWER RATING") "0.25 W")
        (field (name "PACKAGE") "1206")
        (field (name "TOLERANCE") "1 %")
      )
      (libsource (lib "PEF") (part "SMT Resistor"))
    )
    (comp (ref "R24")
      (value "330 Ω")
      (footprint "1206_GENERIC")
      (description "Generic SMT Resistor")
      (fields
        (field (name "PART NUMBER") "RC1206FR-07330RL")
        (field (name "MANUFACTURER") "Yageo")
        (field (name "POWER RATING") "0.25 W")
        (field (name "PACKAGE") "1206")
        (field (name "TOLERANCE") "1 %")
      )
      (libsource (lib "PEF") (part "SMT Resistor"))
    )
    (comp (ref "R25")
      (value "330 Ω")
      (footprint "1206_GENERIC")
      (description "Generic SMT Resistor")
      (fields
        (field (name "PART NUMBER") "RC1206FR-07330RL")
        (field (name "MANUFACTURER") "Yageo")
        (field (name "POWER RATING") "0.25 W")
        (field (name "PACKAGE") "1206")
        (field (name "TOLERANCE") "1 %")
      )
      (libsource (lib "PEF") (part "SMT Resistor"))
    )
    (comp (ref "R26")
      (value "100 KΩ")
      (footprint "1206_GENERIC")
      (description "Generic SMT Resistor")
      (fields
        (field (name "PART NUMBER") "RC1206FR-07100KL")
        (field (name "MANUFACTURER") "Yageo")
        (field (name "POWER RATING") "0.25 W")
        (field (name "PACKAGE") "1206")
        (field (name "TOLERANCE") "1 %")
      )
      (libsource (lib "PEF") (part "SMT Resistor"))
    )
    (comp (ref "R27")
      (value "10 KΩ")
      (footprint "1206_GENERIC")
      (description "Generic SMT Resistor")
      (fields
        (field (name "PART NUMBER") "RC1206FR-0710KL")
        (field (name "MANUFACTURER") "Yageo")
        (field (name "POWER RATING") "0.25 W")
        (field (name "PACKAGE") "1206")
        (field (name "TOLERANCE") "1 %")
      )
      (libsource (lib "PEF") (part "SMT Resistor"))
    )
    (comp (ref "R28")
      (value "1 KΩ")
      (footprint "1206_GENERIC")
      (description "Generic SMT Resistor")
      (fields
        (field (name "PART NUMBER") "RC1206FR-071KL")
        (field (name "MANUFACTURER") "Yageo")
        (field (name "POWER RATING") "0.25 W")
        (field (name "PACKAGE") "1206")
        (field (name "TOLERANCE") "1 %")
      )
      (libsource (lib "PEF") (part "SMT Resistor"))
    )
    (comp (ref "R29")
      (value "10 KΩ")
      (footprint "1206_GENERIC")
      (description "Generic SMT Resistor")
      (fields
        (field (name "PART NUMBER") "RC1206FR-0710KL")
        (field (name "MANUFACTURER") "Yageo")
        (field (name "POWER RATING") "0.25 W")
        (field (name "PACKAGE") "1206")
        (field (name "TOLERANCE") "1 %")
      )
      (libsource (lib "PEF") (part "SMT Resistor"))
    )
    (comp (ref "R30")
      (value "10 KΩ")
      (footprint "1206_GENERIC")
      (description "Generic SMT Resistor")
      (fields
        (field (name "PART NUMBER") "RC1206FR-0710KL")
        (field (name "MANUFACTURER") "Yageo")
        (field (name "POWER RATING") "0.25 W")
        (field (name "PACKAGE") "1206")
        (field (name "TOLERANCE") "1 %")
      )
      (libsource (lib "PEF") (part "SMT Resistor"))
    )
    (comp (ref "R31")
      (value "10 KΩ")
      (footprint "1206_GENERIC")
      (description "Generic SMT Resistor")
      (fields
        (field (name "PART NUMBER") "RC1206FR-0710KL")
        (field (name "MANUFACTURER") "Yageo")
        (field (name "POWER RATING") "0.25 W")
        (field (name "PACKAGE") "1206")
        (field (name "TOLERANCE") "1 %")
      )
      (libsource (lib "PEF") (part "SMT Resistor"))
    )
    (comp (ref "R32")
      (value "100 KΩ")
      (footprint "1206_GENERIC")
      (description "Generic SMT Resistor")
      (fields
        (field (name "PART NUMBER") "RC1206FR-07100KL")
        (field (name "MANUFACTURER") "Yageo")
        (field (name "POWER RATING") "0.25 W")
        (field (name "PACKAGE") "1206")
        (field (name "TOLERANCE") "1 %")
      )
      (libsource (lib "PEF") (part "SMT Resistor"))
    )
    (comp (ref "R33")
      (value "100 KΩ")
      (footprint "1206_GENERIC")
      (description "Generic SMT Resistor")
      (fields
        (field (name "PART NUMBER") "RC1206FR-07100KL")
        (field (name "MANUFACTURER") "Yageo")
        (field (name "POWER RATING") "0.25 W")
        (field (name "PACKAGE") "1206")
        (field (name "TOLERANCE") "1 %")
      )
      (libsource (lib "PEF") (part "SMT Resistor"))
    )
    (comp (ref "R34")
      (value "1 KΩ")
      (footprint "1206_GENERIC")
      (description "Generic SMT Resistor")
      (fields
        (field (name "PART NUMBER") "RC1206FR-071KL")
        (field (name "MANUFACTURER") "Yageo")
        (field (name "POWER RATING") "0.25 W")
        (field (name "PACKAGE") "1206")
        (field (name "TOLERANCE") "1 %")
      )
      (libsource (lib "PEF") (part "SMT Resistor"))
    )
    (comp (ref "R35")
      (value "10 KΩ")
      (footprint "1206_GENERIC")
      (description "Generic SMT Resistor")
      (fields
        (field (name "PART NUMBER") "RC1206FR-0710KL")
        (field (name "MANUFACTURER") "Yageo")
        (field (name "POWER RATING") "0.25 W")
        (field (name "PACKAGE") "1206")
        (field (name "TOLERANCE") "1 %")
      )
      (libsource (lib "PEF") (part "SMT Resistor"))
    )
    (comp (ref "R36")
      (value "100 KΩ")
      (footprint "1206_GENERIC")
      (description "Generic SMT Resistor")
      (fields
        (field (name "PART NUMBER") "RC1206FR-07100KL")
        (field (name "MANUFACTURER") "Yageo")
        (field (name "POWER RATING") "0.25 W")
        (field (name "PACKAGE") "1206")
        (field (name "TOLERANCE") "1 %")
      )
      (libsource (lib "PEF") (part "SMT Resistor"))
    )
    (comp (ref "R37")
      (value "10 KΩ")
      (footprint "1206_GENERIC")
      (description "Generic SMT Resistor")
      (fields
        (field (name "PART NUMBER") "RC1206FR-0710KL")
        (field (name "MANUFACTURER") "Yageo")
        (field (name "POWER RATING") "0.25 W")
        (field (name "PACKAGE") "1206")
        (field (name "TOLERANCE") "1 %")
      )
      (libsource (lib "PEF") (part "SMT Resistor"))
    )
    (comp (ref "R38")
      (value "100 KΩ")
      (footprint "1206_GENERIC")
      (description "Generic SMT Resistor")
      (fields
        (field (name "PART NUMBER") "RC1206FR-07100KL")
        (field (name "MANUFACTURER") "Yageo")
        (field (name "POWER RATING") "0.25 W")
        (field (name "PACKAGE") "1206")
        (field (name "TOLERANCE") "1 %")
      )
      (libsource (lib "PEF") (part "SMT Resistor"))
    )
    (comp (ref "R39")
      (value "10 KΩ")
      (footprint "1206_GENERIC")
      (description "Generic SMT Resistor")
      (fields
        (field (name "PART NUMBER") "RC1206FR-0710KL")
        (field (name "MANUFACTURER") "Yageo")
        (field (name "POWER RATING") "0.25 W")
        (field (name "PACKAGE") "1206")
        (field (name "TOLERANCE") "1 %")
      )
      (libsource (lib "PEF") (part "SMT Resistor"))
    )
    (comp (ref "R40")
      (value "100 KΩ")
      (footprint "1206_GENERIC")
      (description "Generic SMT Resistor")
      (fields
        (field (name "PART NUMBER") "RC1206FR-07100KL")
        (field (name "MANUFACTURER") "Yageo")
        (field (name "POWER RATING") "0.25 W")
        (field (name "PACKAGE") "1206")
        (field (name "TOLERANCE") "1 %")
      )
      (libsource (lib "PEF") (part "SMT Resistor"))
    )
    (comp (ref "R41")
      (value "100 KΩ")
      (footprint "1206_GENERIC")
      (description "Generic SMT Resistor")
      (fields
        (field (name "PART NUMBER") "RC1206FR-07100KL")
        (field (name "MANUFACTURER") "Yageo")
        (field (name "POWER RATING") "0.25 W")
        (field (name "PACKAGE") "1206")
        (field (name "TOLERANCE") "1 %")
      )
      (libsource (lib "PEF") (part "SMT Resistor"))
    )
    (comp (ref "R42")
      (value "100 KΩ")
      (footprint "1206_GENERIC")
      (description "Generic SMT Resistor")
      (fields
        (field (name "PART NUMBER") "RC1206FR-07100KL")
        (field (name "MANUFACTURER") "Yageo")
        (field (name "POWER RATING") "0.25 W")
        (field (name "PACKAGE") "1206")
        (field (name "TOLERANCE") "1 %")
      )
      (libsource (lib "PEF") (part "SMT Resistor"))
    )
    (comp (ref "R43")
      (value "100 KΩ")
      (footprint "1206_GENERIC")
      (description "Generic SMT Resistor")
      (fields
        (field (name "PART NUMBER") "RC1206FR-07100KL")
        (field (name "MANUFACTURER") "Yageo")
        (field (name "POWER RATING") "0.25 W")
        (field (name "PACKAGE") "1206")
        (field (name "TOLERANCE") "1 %")
      )
      (libsource (lib "PEF") (part "SMT Resistor"))
    )
    (comp (ref "R44")
      (value "100 KΩ")
      (footprint "1206_GENERIC")
      (description "Generic SMT Resistor")
      (fields
        (field (name "PART NUMBER") "RC1206FR-07100KL")
        (field (name "MANUFACTURER") "Yageo")
        (field (name "POWER RATING") "0.25 W")
        (field (name "PACKAGE") "1206")
        (field (name "TOLERANCE") "1 %")
      )
      (libsource (lib "PEF") (part "SMT Resistor"))
    )
    (comp (ref "R45")
      (value "100 KΩ")
      (footprint "1206_GENERIC")
      (description "Generic SMT Resistor")
      (fields
        (field (name "PART NUMBER") "RC1206FR-07100KL")
        (field (name "MANUFACTURER") "Yageo")
        (field (name "POWER RATING") "0.25 W")
        (field (name "PACKAGE") "1206")
        (field (name "TOLERANCE") "1 %")
      )
      (libsource (lib "PEF") (part "SMT Resistor"))
    )
    (comp (ref "R46")
      (value "100 KΩ")
      (footprint "1206_GENERIC")
      (description "Generic SMT Resistor")
      (fields
        (field (name "PART NUMBER") "RC1206FR-07100KL")
        (field (name "MANUFACTURER") "Yageo")
        (field (name "POWER RATING") "0.25 W")
        (field (name "PACKAGE") "1206")
        (field (name "TOLERANCE") "1 %")
      )
      (libsource (lib "PEF") (part "SMT Resistor"))
    )
    (comp (ref "R47")
      (value "100 KΩ")
      (footprint "1206_GENERIC")
      (description "Generic SMT Resistor")
      (fields
        (field (name "PART NUMBER") "RC1206FR-07100KL")
        (field (name "MANUFACTURER") "Yageo")
        (field (name "POWER RATING") "0.25 W")
        (field (name "PACKAGE") "1206")
        (field (name "TOLERANCE") "1 %")
      )
      (libsource (lib "PEF") (part "SMT Resistor"))
    )
    (comp (ref "R48")
      (value "100 KΩ")
      (footprint "1206_GENERIC")
      (description "Generic SMT Resistor")
      (fields
        (field (name "PART NUMBER") "RC1206FR-07100KL")
        (field (name "MANUFACTURER") "Yageo")
        (field (name "POWER RATING") "0.25 W")
        (field (name "PACKAGE") "1206")
        (field (name "TOLERANCE") "1 %")
      )
      (libsource (lib "PEF") (part "SMT Resistor"))
    )
    (comp (ref "R49")
      (value "100 KΩ")
      (footprint "1206_GENERIC")
      (description "Generic SMT Resistor")
      (fields
        (field (name "PART NUMBER") "RC1206FR-07100KL")
        (field (name "MANUFACTURER") "Yageo")
        (field (name "POWER RATING") "0.25 W")
        (field (name "PACKAGE") "1206")
        (field (name "TOLERANCE") "1 %")
      )
      (libsource (lib "PEF") (part "SMT Resistor"))
    )
    (comp (ref "R50")
      (value "100 KΩ")
      (footprint "1206_GENERIC")
      (description "Generic SMT Resistor")
      (fields
        (field (name "PART NUMBER") "RC1206FR-07100KL")
        (field (name "MANUFACTURER") "Yageo")
        (field (name "POWER RATING") "0.25 W")
        (field (name "PACKAGE") "1206")
        (field (name "TOLERANCE") "1 %")
      )
      (libsource (lib "PEF") (part "SMT Resistor"))
    )
    (comp (ref "R51")
      (value "100 KΩ")
      (footprint "1206_GENERIC")
      (description "Generic SMT Resistor")
      (fields
        (field (name "PART NUMBER") "RC1206FR-07100KL")
        (field (name "MANUFACTURER") "Yageo")
        (field (name "POWER RATING") "0.25 W")
        (field (name "PACKAGE") "1206")
        (field (name "TOLERANCE") "1 %")
      )
      (libsource (lib "PEF") (part "SMT Resistor"))
    )
    (comp (ref "TACT")
      (value "APTD3216CGCK")
      (footprint "KING-APTD3216CGCK_V")
      (description "Chip LED Lamp, Green, 5 V, 30 mA, -40 to 85 degC, 2-Pin SMD, RoHS, Tape and Reel")
      (fields (field (name "MANUFACTURER") "Kingbright"))
      (libsource (lib "Altium Content Vault") (part "LED-GREEN-AK-2"))
    )
    (comp (ref "TNCi")
      (value "5019")
      (footprint "KSTN-5019_V")
      (description "Test Point, 1 Position SMD, RoHS, Tape and Reel")
      (fields (field (name "MANUFACTURER") "Keystone Electronics"))
      (libsource (lib "Altium Content Vault") (part "TESTPOINT_WHITE"))
    )
    (comp (ref "TNCo")
      (value "5019")
      (footprint "KSTN-5019_V")
      (description "Test Point, 1 Position SMD, RoHS, Tape and Reel")
      (fields (field (name "MANUFACTURER") "Keystone Electronics"))
      (libsource (lib "Altium Content Vault") (part "TESTPOINT_WHITE"))
    )
    (comp (ref "TNC_EGY")
      (value "APTD3216CGCK")
      (footprint "KING-APTD3216CGCK_V")
      (description "Chip LED Lamp, Green, 5 V, 30 mA, -40 to 85 degC, 2-Pin SMD, RoHS, Tape and Reel")
      (fields (field (name "MANUFACTURER") "Kingbright"))
      (libsource (lib "Altium Content Vault") (part "LED-GREEN-AK-2"))
    )
    (comp (ref "TNC_FSK_RX")
      (value "5019")
      (footprint "KSTN-5019_V")
      (description "Test Point, 1 Position SMD, RoHS, Tape and Reel")
      (fields (field (name "MANUFACTURER") "Keystone Electronics"))
      (libsource (lib "Altium Content Vault") (part "TESTPOINT_WHITE"))
    )
    (comp (ref "TNC_FSK_TX")
      (value "5019")
      (footprint "KSTN-5019_V")
      (description "Test Point, 1 Position SMD, RoHS, Tape and Reel")
      (fields (field (name "MANUFACTURER") "Keystone Electronics"))
      (libsource (lib "Altium Content Vault") (part "TESTPOINT_WHITE"))
    )
    (comp (ref "TNC_PROG")
      (value "Header 5")
      (footprint "HDR1X5")
      (description "Header, 5-Pin")
      (fields (field (name "PUBLISHER") "Altium Limited"))
      (libsource (lib "Miscellaneous Connectors") (part "Header 5"))
    )
    (comp (ref "TNC_PTT")
      (value "APTD3216CGCK")
      (footprint "KING-APTD3216CGCK_V")
      (description "Chip LED Lamp, Green, 5 V, 30 mA, -40 to 85 degC, 2-Pin SMD, RoHS, Tape and Reel")
      (fields (field (name "MANUFACTURER") "Kingbright"))
      (libsource (lib "Altium Content Vault") (part "LED-GREEN-AK-2"))
    )
    (comp (ref "U1")
      (value "SN74LVC2G125DCTR")
      (footprint "DCT0008A_M")
      (description "Dual Bus Buffer Gate with 3-State Outputs, DCT0008A, LARGE T&R")
      (fields
        (field (name "MANUFACTURER") "Texas Instruments")
        (field (name "GENERIC PART NUMBER") "SN74LVC2G125")
      )
      (libsource (lib "Altium Content Vault") (part "TI-SN74XXX2G125-XX-8"))
    )
    (comp (ref "U2")
      (value "SN74LVC2G04DBVT")
      (footprint "DBV0006A_M")
      (description "Dual Inverter, DBV0006A, SMALL T&R")
      (fields
        (field (name "GENERIC PART NUMBER") "SN74LVC2G04")
        (field (name "MANUFACTURER") "Texas Instruments")
      )
      (libsource (lib "Altium Content Vault") (part "TI-SN74XXX2GXXX-6"))
    )
    (comp (ref "U3")
      (value "PCA9554DWR")
      (footprint "DW0016A_M")
      (fields (field (name "MANUFACTURER") "Texas Instruments"))
      (libsource (lib "Altium Content Vault") (part "TI-PCA9554-SOIC_DW-16"))
    )
    (comp (ref "U4")
      (value "DS2482S-100+")
      (footprint "MAXM-SO-8_V")
      (description "Single-Channel 1-Wire Master, 2.9 to 5.5 V, -40 to 85 degC, 8-Pin SO, RoHS, Rail/Tube")
      (fields (field (name "MANUFACTURER") "Maxim"))
      (libsource (lib "Altium Content Vault") (part "MAXM-DS2482S-100-SO-8"))
    )
    (comp (ref "U5")
      (value "MX614TN")
      (footprint "PEF_LIB:24SSOP150_M")
      (fields (field (name "MANUFACTURER") "CML Microcircuits"))
      (libsource (lib "PEF") (part "MX614"))
    )
    (comp (ref "U6")
      (value "PIC16F1847-I/SS")
      (footprint "MCHP-SSOP-SS20_M")
      (fields (field (name "MANUFACTURER") "Microchip"))
      (libsource (lib "Altium Content Vault") (part "MCHP-PIC16F1847-SSOP-20"))
    )
    (comp (ref "U7")
      (value "MCP6023-I/SN")
      (footprint "SOIC-SN8_L")
      (description "Rail-to-Rail Input/Output, 10 MHz Operational Amplifier, 8-Pin SOIC, Industrial Temperature")
      (fields (field (name "MANUFACTURER") "Microchip"))
      (libsource (lib "Altium Content Vault") (part "AMP-OPA-MCP6023-IL8"))
    )
    (comp (ref "U8")
      (value "23K640-I/ST")
      (footprint "TSSOP-ST8_M")
      (description "64K, 8192x8-bit, 3.6V SPI Serial SRAM, 8-Pin TSSOP, Industrial Temperature")
      (fields (field (name "MANUFACTURER") "Microchip"))
      (libsource (lib "Altium Content Vault") (part "MEM-SERAM-23A640-IL8"))
    )
    (comp (ref "U9")
      (value "ADG2188BCPZ-REEL7")
      (footprint "ADI-CP-32-2_M")
      (fields (field (name "MANUFACTURER") "Analog Devices"))
      (libsource (lib "Altium Content Vault") (part "ADI-ADG2188-CP-32-2"))
    )
    (comp (ref "UACT")
      (value "APTD3216CGCK")
      (footprint "KING-APTD3216CGCK_V")
      (description "Chip LED Lamp, Green, 5 V, 30 mA, -40 to 85 degC, 2-Pin SMD, RoHS, Tape and Reel")
      (fields (field (name "MANUFACTURER") "Kingbright"))
      (libsource (lib "Altium Content Vault") (part "LED-GREEN-AK-2"))
    )
    (comp (ref "UHF")
      (value "APTD3216CGCK")
      (footprint "KING-APTD3216CGCK_V")
      (description "Chip LED Lamp, Green, 5 V, 30 mA, -40 to 85 degC, 2-Pin SMD, RoHS, Tape and Reel")
      (fields (field (name "MANUFACTURER") "Kingbright"))
      (libsource (lib "Altium Content Vault") (part "LED-GREEN-AK-2"))
    )
    (comp (ref "UHFC")
      (value "~")
      (footprint "CAPE-3 IBC:Molex 87758-1816")
      (description "Header, 9-Pin, Dual row")
      (fields
        (field (name "PART NUMBER") "63453-118LF")
        (field (name "MANUFACTURER") "Amphenol")
        (field (name "PUBLISHER") "Altium Limited")
      )
      (libsource (lib "Miscellaneous Connectors") (part "Header 9X2"))
    )
    (comp (ref "UHFi")
      (value "5019")
      (footprint "KSTN-5019_V")
      (description "Test Point, 1 Position SMD, RoHS, Tape and Reel")
      (fields (field (name "MANUFACTURER") "Keystone Electronics"))
      (libsource (lib "Altium Content Vault") (part "TESTPOINT_WHITE"))
    )
    (comp (ref "UHFo")
      (value "5019")
      (footprint "KSTN-5019_V")
      (description "Test Point, 1 Position SMD, RoHS, Tape and Reel")
      (fields (field (name "MANUFACTURER") "Keystone Electronics"))
      (libsource (lib "Altium Content Vault") (part "TESTPOINT_WHITE"))
    )
    (comp (ref "UHF_TRANS")
      (value "5019")
      (footprint "KSTN-5019_V")
      (description "Test Point, 1 Position SMD, RoHS, Tape and Reel")
      (fields (field (name "MANUFACTURER") "Keystone Electronics"))
      (libsource (lib "Altium Content Vault") (part "TESTPOINT_WHITE"))
    )
    (comp (ref "USB1")
      (value "1734346-1")
      (footprint "TECO-1734346-1_V")
      (description "USB-B Receptacle Connector, Height 10.87 mm, 0 to 50 degC, RoHS, Tray")
      (fields (field (name "MANUFACTURER") "TE Connectivity") (field (name "PART NUMBER") "1-1734346-1"))
      (libsource (lib "Altium Content Vault") (part "USB-4-2SHLD"))
    )
    (comp (ref "VACT")
      (value "APTD3216CGCK")
      (footprint "KING-APTD3216CGCK_V")
      (description "Chip LED Lamp, Green, 5 V, 30 mA, -40 to 85 degC, 2-Pin SMD, RoHS, Tape and Reel")
      (fields (field (name "MANUFACTURER") "Kingbright"))
      (libsource (lib "Altium Content Vault") (part "LED-GREEN-AK-2"))
    )
    (comp (ref "Vbus")
      (value "5019")
      (footprint "KSTN-5019_V")
      (description "Test Point, 1 Position SMD, RoHS, Tape and Reel")
      (fields (field (name "MANUFACTURER") "Keystone Electronics"))
      (libsource (lib "Altium Content Vault") (part "TESTPOINT_WHITE"))
    )
    (comp (ref "Vbus_f")
      (value "5019")
      (footprint "KSTN-5019_V")
      (description "Test Point, 1 Position SMD, RoHS, Tape and Reel")
      (fields (field (name "MANUFACTURER") "Keystone Electronics"))
      (libsource (lib "Altium Content Vault") (part "TESTPOINT_WHITE"))
    )
    (comp (ref "VHF")
      (value "APTD3216CGCK")
      (footprint "KING-APTD3216CGCK_V")
      (description "Chip LED Lamp, Green, 5 V, 30 mA, -40 to 85 degC, 2-Pin SMD, RoHS, Tape and Reel")
      (fields (field (name "MANUFACTURER") "Kingbright"))
      (libsource (lib "Altium Content Vault") (part "LED-GREEN-AK-2"))
    )
    (comp (ref "VHFC")
      (value "~")
      (footprint "CAPE-3 IBC:Molex 87758-1816")
      (description "Header, 9-Pin, Dual row")
      (fields
        (field (name "PART NUMBER") "63453-118LF")
        (field (name "MANUFACTURER") "Amphenol")
        (field (name "PUBLISHER") "Altium Limited")
      )
      (libsource (lib "Miscellaneous Connectors") (part "Header 9X2"))
    )
    (comp (ref "VHFi")
      (value "5019")
      (footprint "KSTN-5019_V")
      (description "Test Point, 1 Position SMD, RoHS, Tape and Reel")
      (fields (field (name "MANUFACTURER") "Keystone Electronics"))
      (libsource (lib "Altium Content Vault") (part "TESTPOINT_WHITE"))
    )
    (comp (ref "VHFo")
      (value "5019")
      (footprint "KSTN-5019_V")
      (description "Test Point, 1 Position SMD, RoHS, Tape and Reel")
      (fields (field (name "MANUFACTURER") "Keystone Electronics"))
      (libsource (lib "Altium Content Vault") (part "TESTPOINT_WHITE"))
    )
    (comp (ref "VHF_TRANS")
      (value "5019")
      (footprint "KSTN-5019_V")
      (description "Test Point, 1 Position SMD, RoHS, Tape and Reel")
      (fields (field (name "MANUFACTURER") "Keystone Electronics"))
      (libsource (lib "Altium Content Vault") (part "TESTPOINT_WHITE"))
    )
    (comp (ref "Y1")
      (value "ABM3B-20.000MHZ-B2-T")
      (footprint "ABRA-ABM3B_V")
      (description "Ceramic SMD Crystal, 8 MHz, +/- 20 ppm, 200 Ohm, -20 to 70 degC, 4-Pin SMD, RoHS, Tape and Reel")
      (fields (field (name "MANUFACTURER") "Abracon"))
      (libsource (lib "Altium Content Vault") (part "XTAL-1-3-4"))
    )
    (comp (ref "Y2")
      (value "ECS-035-18-4X-DU")
      (footprint "ECS-4X-3IL")
      (description "CRYSTAL 8.00 MHZ 20PF 49US")
      (fields (field (name "MANUFACTURER") "ECS"))
      (libsource (lib "Altium Content Vault") (part "ECS-ECS-XX-20-4X"))
    )
  )
  (nets
    (net (code "1") (name "/ADC1_9_COM_VHF_RFS") (class "Default")
      (node (ref "VHFC") (pin "15") (pinfunction "15_15") (pintype "input+no_connect"))
    )
    (net (code "2") (name "/COM_UHF_AUD_IN") (class "Default")
      (node (ref "C26") (pin "2") (pinfunction "2_2") (pintype "passive"))
      (node (ref "UHFC") (pin "15") (pinfunction "15_15") (pintype "input"))
      (node (ref "UHFi") (pin "1") (pinfunction "1_1") (pintype "passive"))
    )
    (net (code "3") (name "/COM_UHF_AUD_OUT") (class "Default")
      (node (ref "C27") (pin "2") (pinfunction "2_2") (pintype "passive"))
      (node (ref "UHFC") (pin "18") (pinfunction "18_18") (pintype "output"))
      (node (ref "UHFo") (pin "1") (pinfunction "1_1") (pintype "passive"))
    )
    (net (code "4") (name "/COM_UHF_BP") (class "Default")
      (node (ref "DBG1") (pin "13") (pinfunction "13_13") (pintype "passive"))
      (node (ref "N5") (pin "8") (pinfunction "8_8") (pintype "output"))
      (node (ref "UHFC") (pin "6") (pinfunction "6_6") (pintype "input"))
    )
    (net (code "5") (name "/COM_UHF_EN{slash}~{DIS}") (class "Default")
      (node (ref "DBG1") (pin "9") (pinfunction "9_9") (pintype "passive"))
      (node (ref "N8") (pin "6") (pinfunction "6_6") (pintype "output"))
      (node (ref "UHFC") (pin "4") (pinfunction "4_4") (pintype "input"))
    )
    (net (code "6") (name "/COM_UHF_RFS") (class "Default")
      (node (ref "UHFC") (pin "14") (pinfunction "14_14") (pintype "passive+no_connect"))
    )
    (net (code "7") (name "/COM_UHF_TOP{slash}~{BOT}") (class "Default")
      (node (ref "DBG1") (pin "15") (pinfunction "15_15") (pintype "passive"))
      (node (ref "N5") (pin "9") (pinfunction "9_9") (pintype "output"))
      (node (ref "UHFC") (pin "8") (pinfunction "8_8") (pintype "input"))
    )
    (net (code "8") (name "/COM_UHF_TX{slash}~{RX}") (class "Default")
      (node (ref "DBG1") (pin "7") (pinfunction "7_7") (pintype "passive"))
      (node (ref "N8") (pin "4") (pinfunction "4_4") (pintype "output"))
      (node (ref "UHFC") (pin "2") (pinfunction "2_2") (pintype "input"))
      (node (ref "UHF_TRANS") (pin "1") (pinfunction "1_1") (pintype "passive"))
    )
    (net (code "9") (name "/COM_VHF_AUD_IN") (class "Default")
      (node (ref "C30") (pin "2") (pinfunction "2_2") (pintype "passive"))
      (node (ref "VHFC") (pin "6") (pinfunction "6_6") (pintype "input"))
      (node (ref "VHFi") (pin "1") (pinfunction "1_1") (pintype "passive"))
    )
    (net (code "10") (name "/COM_VHF_AUD_OUT") (class "Default")
      (node (ref "C31") (pin "2") (pinfunction "2_2") (pintype "passive"))
      (node (ref "VHFC") (pin "4") (pinfunction "4_4") (pintype "input"))
      (node (ref "VHFo") (pin "1") (pinfunction "1_1") (pintype "passive"))
    )
    (net (code "11") (name "/COM_VHF_HP{slash}~{LP}") (class "Default")
      (node (ref "DBG1") (pin "23") (pinfunction "23_23") (pintype "passive"))
      (node (ref "N9") (pin "2") (pinfunction "2_2") (pintype "output"))
      (node (ref "VHFC") (pin "16") (pinfunction "16_16") (pintype "bidirectional"))
    )
    (net (code "12") (name "/COM_VHF_TOP{slash}~{BOT}") (class "Default")
      (node (ref "DBG1") (pin "17") (pinfunction "17_17") (pintype "passive"))
      (node (ref "N9") (pin "1") (pinfunction "1_1") (pintype "output"))
      (node (ref "VHFC") (pin "12") (pinfunction "12_12") (pintype "power_in"))
    )
    (net (code "13") (name "/COM_VHF_TX{slash}~{RX}") (class "Default")
      (node (ref "DBG1") (pin "19") (pinfunction "19_19") (pintype "passive"))
      (node (ref "N8") (pin "5") (pinfunction "5_5") (pintype "output"))
      (node (ref "VHFC") (pin "14") (pinfunction "14_14") (pintype "passive"))
      (node (ref "VHF_TRANS") (pin "1") (pinfunction "1_1") (pintype "passive"))
    )
    (net (code "14") (name "/DEBUG_LED_4") (class "Default")
      (node (ref "DBG1") (pin "29") (pinfunction "29_29") (pintype "passive"))
      (node (ref "DS4") (pin "1") (pinfunction "A_1") (pintype "passive"))
      (node (ref "U3") (pin "9") (pinfunction "P4_9") (pintype "bidirectional"))
    )
    (net (code "15") (name "/DEBUG_LED_5") (class "Default")
      (node (ref "DS5") (pin "1") (pinfunction "A_1") (pintype "passive"))
      (node (ref "U3") (pin "10") (pinfunction "P5_10") (pintype "bidirectional"))
    )
    (net (code "16") (name "/DEBUG_LED_6") (class "Default")
      (node (ref "DS6") (pin "1") (pinfunction "A_1") (pintype "passive"))
      (node (ref "U3") (pin "11") (pinfunction "P6_11") (pintype "bidirectional"))
    )
    (net (code "17") (name "/DEBUG_LED_7") (class "Default")
      (node (ref "DS7") (pin "1") (pinfunction "A_1") (pintype "passive"))
      (node (ref "U3") (pin "12") (pinfunction "P7_12") (pintype "bidirectional"))
    )
    (net (code "18") (name "/I2C1_SCL_OUT") (class "Default")
      (node (ref "DBG1") (pin "3") (pinfunction "3_3") (pintype "passive"))
      (node (ref "R4") (pin "2") (pinfunction "2_2") (pintype "passive"))
      (node (ref "U3") (pin "14") (pinfunction "SCL_14") (pintype "input"))
      (node (ref "U4") (pin "4") (pinfunction "SCL_4") (pintype "input"))
      (node (ref "U9") (pin "27") (pinfunction "SCL_27") (pintype "input"))
    )
    (net (code "19") (name "/I2C1_SCL_ST") (class "Default")
      (node (ref "N5") (pin "1") (pinfunction "1_1") (pintype "output"))
      (node (ref "R3") (pin "1") (pinfunction "1_1") (pintype "passive"))
    )
    (net (code "20") (name "/I2C1_SDA_OUT") (class "Default")
      (node (ref "DBG1") (pin "5") (pinfunction "5_5") (pintype "passive"))
      (node (ref "R6") (pin "2") (pinfunction "2_2") (pintype "passive"))
      (node (ref "U3") (pin "15") (pinfunction "SDA_15") (pintype "bidirectional"))
      (node (ref "U4") (pin "5") (pinfunction "SDA_5") (pintype "bidirectional"))
      (node (ref "U9") (pin "26") (pinfunction "SDA_26") (pintype "bidirectional"))
    )
    (net (code "21") (name "/I2C1_SDA_ST") (class "Default")
      (node (ref "N5") (pin "2") (pinfunction "2_2") (pintype "bidirectional"))
      (node (ref "R5") (pin "1") (pinfunction "1_1") (pintype "passive"))
    )
    (net (code "22") (name "/MUX_RST") (class "Default")
      (node (ref "U3") (pin "4") (pinfunction "P0_4") (pintype "bidirectional"))
      (node (ref "U9") (pin "31") (pinfunction "~{RESET}_31") (pintype "input"))
    )
    (net (code "23") (name "/MUX_X0") (class "Default")
      (node (ref "C26") (pin "1") (pinfunction "1_1") (pintype "passive"))
      (node (ref "R40") (pin "1") (pinfunction "1_1") (pintype "passive"))
      (node (ref "R46") (pin "2") (pinfunction "2_2") (pintype "passive"))
      (node (ref "U9") (pin "3") (pinfunction "X0_3") (pintype "output"))
    )
    (net (code "24") (name "/MUX_X1") (class "Default")
      (node (ref "C27") (pin "1") (pinfunction "1_1") (pintype "passive"))
      (node (ref "R41") (pin "1") (pinfunction "1_1") (pintype "passive"))
      (node (ref "R47") (pin "2") (pinfunction "2_2") (pintype "passive"))
      (node (ref "U9") (pin "4") (pinfunction "X1_4") (pintype "input"))
    )
    (net (code "25") (name "/MUX_X2") (class "Default")
      (node (ref "C30") (pin "1") (pinfunction "1_1") (pintype "passive"))
      (node (ref "R42") (pin "1") (pinfunction "1_1") (pintype "passive"))
      (node (ref "R48") (pin "2") (pinfunction "2_2") (pintype "passive"))
      (node (ref "U9") (pin "5") (pinfunction "X2_5") (pintype "output"))
    )
    (net (code "26") (name "/MUX_X3") (class "Default")
      (node (ref "C31") (pin "1") (pinfunction "1_1") (pintype "passive"))
      (node (ref "R43") (pin "1") (pinfunction "1_1") (pintype "passive"))
      (node (ref "R49") (pin "2") (pinfunction "2_2") (pintype "passive"))
      (node (ref "U9") (pin "6") (pinfunction "X3_6") (pintype "input"))
    )
    (net (code "27") (name "/MUX_Y2") (class "Default")
      (node (ref "C34") (pin "1") (pinfunction "1_1") (pintype "passive"))
      (node (ref "R45") (pin "1") (pinfunction "1_1") (pintype "passive"))
      (node (ref "R51") (pin "2") (pinfunction "2_2") (pintype "passive"))
      (node (ref "U9") (pin "11") (pinfunction "Y2_11") (pintype "output"))
    )
    (net (code "28") (name "/MUX_Y3") (class "Default")
      (node (ref "C32") (pin "1") (pinfunction "1_1") (pintype "passive"))
      (node (ref "R44") (pin "1") (pinfunction "1_1") (pintype "passive"))
      (node (ref "R50") (pin "2") (pinfunction "2_2") (pintype "passive"))
      (node (ref "U9") (pin "12") (pinfunction "Y3_12") (pintype "input"))
    )
    (net (code "29") (name "/M_OSC1") (class "Default")
      (node (ref "C24") (pin "2") (pinfunction "2_2") (pintype "passive"))
      (node (ref "U5") (pin "1") (pinfunction "XTAL_OUT_1") (pintype "output"))
      (node (ref "Y2") (pin "1") (pinfunction "1_1") (pintype "passive"))
    )
    (net (code "30") (name "/M_OSC2") (class "Default")
      (node (ref "C25") (pin "2") (pinfunction "2_2") (pintype "passive"))
      (node (ref "U5") (pin "2") (pinfunction "XTAL_IN_2") (pintype "input"))
      (node (ref "Y2") (pin "3") (pinfunction "3_3") (pintype "passive"))
    )
    (net (code "31") (name "/OneWire") (class "Default")
      (node (ref "R22") (pin "2") (pinfunction "2_2") (pintype "passive"))
      (node (ref "U4") (pin "2") (pinfunction "IO_2") (pintype "bidirectional"))
      (node (ref "UHFC") (pin "16") (pinfunction "16_16") (pintype "bidirectional"))
      (node (ref "VHFC") (pin "17") (pinfunction "17_17") (pintype "power_in"))
    )
    (net (code "32") (name "/SPI1_MISO_OUT") (class "Default")
      (node (ref "DBG1") (pin "6") (pinfunction "6_6") (pintype "passive"))
      (node (ref "R12") (pin "2") (pinfunction "2_2") (pintype "passive"))
      (node (ref "U1") (pin "3") (pinfunction "2Y_3") (pintype "tri_state"))
      (node (ref "U1") (pin "6") (pinfunction "1Y_6") (pintype "tri_state"))
    )
    (net (code "33") (name "/SPI1_MISO_ST") (class "Default")
      (node (ref "N9") (pin "3") (pinfunction "3_3") (pintype "input"))
      (node (ref "R11") (pin "1") (pinfunction "1_1") (pintype "passive"))
    )
    (net (code "34") (name "/SPI1_MISO_UHF") (class "Default")
      (node (ref "U1") (pin "2") (pinfunction "1A_2") (pintype "input"))
      (node (ref "UHFC") (pin "9") (pinfunction "9_9") (pintype "output"))
    )
    (net (code "35") (name "/SPI1_MISO_VHF") (class "Default")
      (node (ref "U1") (pin "5") (pinfunction "2A_5") (pintype "input"))
      (node (ref "VHFC") (pin "9") (pinfunction "9_9") (pintype "output"))
    )
    (net (code "36") (name "/SPI1_MOSI_OUT") (class "Default")
      (node (ref "DBG1") (pin "8") (pinfunction "8_8") (pintype "passive"))
      (node (ref "R10") (pin "2") (pinfunction "2_2") (pintype "passive"))
      (node (ref "UHFC") (pin "7") (pinfunction "7_7") (pintype "input"))
      (node (ref "VHFC") (pin "7") (pinfunction "7_7") (pintype "input"))
    )
    (net (code "37") (name "/SPI1_MOSI_ST") (class "Default")
      (node (ref "N9") (pin "4") (pinfunction "4_4") (pintype "output"))
      (node (ref "R9") (pin "1") (pinfunction "1_1") (pintype "passive"))
    )
    (net (code "38") (name "/SPI1_SCK_OUT") (class "Default")
      (node (ref "DBG1") (pin "4") (pinfunction "4_4") (pintype "passive"))
      (node (ref "R8") (pin "2") (pinfunction "2_2") (pintype "passive"))
      (node (ref "UHFC") (pin "11") (pinfunction "11_11") (pintype "input"))
      (node (ref "VHFC") (pin "11") (pinfunction "11_11") (pintype "input"))
    )
    (net (code "39") (name "/SPI1_SCK_ST") (class "Default")
      (node (ref "N9") (pin "5") (pinfunction "5_5") (pintype "output"))
      (node (ref "R7") (pin "1") (pinfunction "1_1") (pintype "passive"))
    )
    (net (code "40") (name "/TNC_ACTIVE") (class "Default")
      (node (ref "DBG1") (pin "20") (pinfunction "20_20") (pintype "passive"))
      (node (ref "TACT") (pin "1") (pinfunction "A_1") (pintype "passive"))
      (node (ref "U3") (pin "7") (pinfunction "P3_7") (pintype "bidirectional"))
    )
    (net (code "41") (name "/TNC_CS") (class "Default")
      (node (ref "U6") (pin "2") (pinfunction "RA3_2") (pintype "bidirectional"))
      (node (ref "U8") (pin "1") (pinfunction "~{CS}_1") (pintype "input"))
    )
    (net (code "42") (name "/TNC_ENERGY") (class "Default")
      (node (ref "DBG1") (pin "30") (pinfunction "30_30") (pintype "passive"))
      (node (ref "R29") (pin "2") (pinfunction "2_2") (pintype "passive"))
      (node (ref "R34") (pin "2") (pinfunction "2_2") (pintype "passive"))
      (node (ref "U6") (pin "3") (pinfunction "RA4_3") (pintype "bidirectional"))
    )
    (net (code "43") (name "/TNC_MRX") (class "Default")
      (node (ref "R31") (pin "2") (pinfunction "2_2") (pintype "passive"))
      (node (ref "TNC_FSK_RX") (pin "1") (pinfunction "1_1") (pintype "passive"))
      (node (ref "U5") (pin "19") (pinfunction "RXD_19") (pintype "output"))
    )
    (net (code "44") (name "/TNC_MTX") (class "Default")
      (node (ref "TNC_FSK_TX") (pin "1") (pinfunction "1_1") (pintype "passive"))
      (node (ref "U5") (pin "17") (pinfunction "TXD_17") (pintype "input"))
      (node (ref "U6") (pin "10") (pinfunction "RB3_10") (pintype "bidirectional"))
    )
    (net (code "45") (name "/TNC_OSC1") (class "Default")
      (node (ref "C22") (pin "2") (pinfunction "2_2") (pintype "passive"))
      (node (ref "U6") (pin "17") (pinfunction "RA6_17") (pintype "bidirectional"))
      (node (ref "Y1") (pin "1") (pinfunction "X1_1") (pintype "passive"))
    )
    (net (code "46") (name "/TNC_OSC2") (class "Default")
      (node (ref "C23") (pin "2") (pinfunction "2_2") (pintype "passive"))
      (node (ref "U6") (pin "18") (pinfunction "RA7_18") (pintype "bidirectional"))
      (node (ref "Y1") (pin "3") (pinfunction "X2_3") (pintype "passive"))
    )
    (net (code "47") (name "/TNC_PGC") (class "Default")
      (node (ref "R31") (pin "1") (pinfunction "1_1") (pintype "passive"))
      (node (ref "TNC_PROG") (pin "5") (pinfunction "5_5") (pintype "passive"))
      (node (ref "U6") (pin "13") (pinfunction "RB6/ICSPCLK_13") (pintype "bidirectional"))
    )
    (net (code "48") (name "/TNC_PGD") (class "Default")
      (node (ref "TNC_PROG") (pin "4") (pinfunction "4_4") (pintype "passive"))
      (node (ref "U5") (pin "6") (pinfunction "M1_6") (pintype "input"))
      (node (ref "U6") (pin "14") (pinfunction "RB7/ICSPDAT_14") (pintype "bidirectional"))
    )
    (net (code "49") (name "/TNC_PTT_IRQ") (class "Default")
      (node (ref "DBG1") (pin "28") (pinfunction "28_28") (pintype "passive"))
      (node (ref "N8") (pin "3") (pinfunction "3_3") (pintype "input"))
      (node (ref "R28") (pin "1") (pinfunction "1_1") (pintype "passive"))
      (node (ref "U5") (pin "5") (pinfunction "M0_5") (pintype "input"))
      (node (ref "U6") (pin "7") (pinfunction "RB0_7") (pintype "bidirectional"))
    )
    (net (code "50") (name "/TNC_SCK") (class "Default")
      (node (ref "U6") (pin "19") (pinfunction "RA0_19") (pintype "bidirectional"))
      (node (ref "U8") (pin "6") (pinfunction "SCK_6") (pintype "input"))
    )
    (net (code "51") (name "/TNC_SIG_IN") (class "Default")
      (node (ref "C14") (pin "2") (pinfunction "2_2") (pintype "passive"))
      (node (ref "C34") (pin "2") (pinfunction "2_2") (pintype "passive"))
      (node (ref "TNCo") (pin "1") (pinfunction "1_1") (pintype "passive"))
    )
    (net (code "52") (name "/TNC_SIG_OUT") (class "Default")
      (node (ref "C15") (pin "2") (pinfunction "2_2") (pintype "passive"))
      (node (ref "C32") (pin "2") (pinfunction "2_2") (pintype "passive"))
      (node (ref "TNCi") (pin "1") (pinfunction "1_1") (pintype "passive"))
    )
    (net (code "53") (name "/TNC_SPI") (class "Default")
      (node (ref "U6") (pin "1") (pinfunction "RA2_1") (pintype "bidirectional"))
      (node (ref "U8") (pin "2") (pinfunction "SO_2") (pintype "output"))
      (node (ref "U8") (pin "5") (pinfunction "SI_5") (pintype "input"))
    )
    (net (code "54") (name "/TNC_~{MCLR}") (class "Default")
      (node (ref "TNC_PROG") (pin "1") (pinfunction "1_1") (pintype "passive"))
      (node (ref "U6") (pin "4") (pinfunction "RA5/~{MCLR}/VPP_4") (pintype "input"))
    )
    (net (code "55") (name "/U1_ST_RX-TNC_TX") (class "Default")
      (node (ref "DBG1") (pin "27") (pinfunction "27_27") (pintype "passive"))
      (node (ref "N9") (pin "6") (pinfunction "6_6") (pintype "input"))
      (node (ref "U6") (pin "12") (pinfunction "RB5_12") (pintype "bidirectional"))
    )
    (net (code "56") (name "/U1_ST_TX-TNC_RX") (class "Default")
      (node (ref "DBG1") (pin "25") (pinfunction "25_25") (pintype "passive"))
      (node (ref "N5") (pin "10") (pinfunction "10_10") (pintype "output"))
      (node (ref "U6") (pin "9") (pinfunction "RB2_9") (pintype "bidirectional"))
    )
    (net (code "57") (name "/UHF_ACTIVE") (class "Default")
      (node (ref "DBG1") (pin "16") (pinfunction "16_16") (pintype "passive"))
      (node (ref "U3") (pin "5") (pinfunction "P1_5") (pintype "bidirectional"))
      (node (ref "UACT") (pin "1") (pinfunction "A_1") (pintype "passive"))
    )
    (net (code "58") (name "/UHF_CS") (class "Default")
      (node (ref "DBG1") (pin "10") (pinfunction "10_10") (pintype "passive"))
      (node (ref "N5") (pin "6") (pinfunction "6_6") (pintype "output"))
      (node (ref "U1") (pin "1") (pinfunction "1~{OE}_1") (pintype "input"))
      (node (ref "U2") (pin "1") (pinfunction "1A_1") (pintype "input"))
      (node (ref "UHFC") (pin "13") (pinfunction "13_13") (pintype "input"))
    )
    (net (code "59") (name "/UHF_IRQ") (class "Default")
      (node (ref "DBG1") (pin "24") (pinfunction "24_24") (pintype "passive"))
      (node (ref "N8") (pin "1") (pinfunction "1_1") (pintype "input"))
      (node (ref "UHFC") (pin "5") (pinfunction "5_5") (pintype "output"))
    )
    (net (code "60") (name "/USB_D_N") (class "Default")
      (node (ref "USB1") (pin "2") (pinfunction "D-_2") (pintype "passive+no_connect"))
    )
    (net (code "61") (name "/USB_D_P") (class "Default")
      (node (ref "USB1") (pin "3") (pinfunction "D+_3") (pintype "passive+no_connect"))
    )
    (net (code "62") (name "/VHF_ACTIVE") (class "Default")
      (node (ref "DBG1") (pin "18") (pinfunction "18_18") (pintype "passive"))
      (node (ref "U3") (pin "6") (pinfunction "P2_6") (pintype "bidirectional"))
      (node (ref "VACT") (pin "1") (pinfunction "A_1") (pintype "passive"))
    )
    (net (code "63") (name "/VHF_CS") (class "Default")
      (node (ref "DBG1") (pin "14") (pinfunction "14_14") (pintype "passive"))
      (node (ref "N5") (pin "7") (pinfunction "7_7") (pintype "output"))
      (node (ref "U1") (pin "7") (pinfunction "2~{OE}_7") (pintype "input"))
      (node (ref "U2") (pin "3") (pinfunction "2A_3") (pintype "input"))
      (node (ref "VHFC") (pin "13") (pinfunction "13_13") (pintype "input"))
    )
    (net (code "64") (name "/VHF_IRQ") (class "Default")
      (node (ref "DBG1") (pin "26") (pinfunction "26_26") (pintype "passive"))
      (node (ref "N8") (pin "2") (pinfunction "2_2") (pintype "input"))
      (node (ref "VHFC") (pin "5") (pinfunction "5_5") (pintype "output"))
    )
    (net (code "65") (name "3V3") (class "Default")
      (node (ref "C1") (pin "1") (pinfunction "1_1") (pintype "passive"))
      (node (ref "C17") (pin "1") (pinfunction "1_1") (pintype "passive"))
      (node (ref "C19") (pin "2") (pinfunction "2_2") (pintype "passive"))
      (node (ref "C20") (pin "2") (pinfunction "2_2") (pintype "passive"))
      (node (ref "C21") (pin "2") (pinfunction "2_2") (pintype "passive"))
      (node (ref "C33") (pin "1") (pinfunction "1_1") (pintype "passive"))
      (node (ref "C7") (pin "1") (pinfunction "1_1") (pintype "passive"))
      (node (ref "C8") (pin "1") (pinfunction "1_1") (pintype "passive"))
      (node (ref "C9") (pin "1") (pinfunction "1_1") (pintype "passive"))
      (node (ref "N5") (pin "3") (pinfunction "3_3") (pintype "power_in"))
      (node (ref "N6") (pin "4") (pinfunction "4_4") (pintype "power_in"))
      (node (ref "R1") (pin "2") (pinfunction "2_2") (pintype "passive"))
      (node (ref "R2") (pin "2") (pinfunction "2_2") (pintype "passive"))
      (node (ref "R22") (pin "1") (pinfunction "1_1") (pintype "passive"))
      (node (ref "R26") (pin "2") (pinfunction "2_2") (pintype "passive"))
      (node (ref "R27") (pin "1") (pinfunction "1_1") (pintype "passive"))
      (node (ref "R29") (pin "1") (pinfunction "1_1") (pintype "passive"))
      (node (ref "R40") (pin "2") (pinfunction "2_2") (pintype "passive"))
      (node (ref "R41") (pin "2") (pinfunction "2_2") (pintype "passive"))
      (node (ref "R42") (pin "2") (pinfunction "2_2") (pintype "passive"))
      (node (ref "R43") (pin "2") (pinfunction "2_2") (pintype "passive"))
      (node (ref "R44") (pin "2") (pinfunction "2_2") (pintype "passive"))
      (node (ref "R45") (pin "2") (pinfunction "2_2") (pintype "passive"))
      (node (ref "TNC_EGY") (pin "1") (pinfunction "A_1") (pintype "passive"))
      (node (ref "TNC_PROG") (pin "2") (pinfunction "2_2") (pintype "passive"))
      (node (ref "U1") (pin "8") (pinfunction "VCC_8") (pintype "power_in"))
      (node (ref "U2") (pin "5") (pinfunction "VCC_5") (pintype "power_in"))
      (node (ref "U3") (pin "16") (pinfunction "VCC_16") (pintype "power_in"))
      (node (ref "U4") (pin "1") (pinfunction "VCC_1") (pintype "power_in"))
      (node (ref "U5") (pin "18") (pinfunction "CLK_18") (pintype "input"))
      (node (ref "U5") (pin "24") (pinfunction "VDD_24") (pintype "power_in"))
      (node (ref "U6") (pin "15") (pinfunction "VDD_15") (pintype "power_in"))
      (node (ref "U6") (pin "16") (pinfunction "VDD_16") (pintype "power_in"))
      (node (ref "U7") (pin "7") (pinfunction "VDD_7") (pintype "power_in"))
      (node (ref "U8") (pin "7") (pinfunction "~{HOLD}_7") (pintype "input"))
      (node (ref "U8") (pin "8") (pinfunction "VCC_8") (pintype "power_in"))
      (node (ref "U9") (pin "24") (pinfunction "VDD_24") (pintype "power_in"))
      (node (ref "U9") (pin "25") (pinfunction "VL_25") (pintype "power_in"))
      (node (ref "UHFC") (pin "17") (pinfunction "17_17") (pintype "power_in"))
      (node (ref "UHFC") (pin "3") (pinfunction "3_3") (pintype "power_in"))
      (node (ref "VHFC") (pin "2") (pinfunction "2_2") (pintype "input"))
      (node (ref "VHFC") (pin "3") (pinfunction "3_3") (pintype "power_in"))
    )
    (net (code "66") (name "5VOUT") (class "Default")
      (node (ref "N6") (pin "5") (pinfunction "5_5") (pintype "power_in"))
    )
    (net (code "67") (name "GND") (class "Default")
      (node (ref "C1") (pin "2") (pinfunction "2_2") (pintype "passive"))
      (node (ref "C13") (pin "2") (pinfunction "2_2") (pintype "passive"))
      (node (ref "C16") (pin "1") (pinfunction "1_1") (pintype "passive"))
      (node (ref "C17") (pin "2") (pinfunction "2_2") (pintype "passive"))
      (node (ref "C19") (pin "1") (pinfunction "1_1") (pintype "passive"))
      (node (ref "C2") (pin "1") (pinfunction "1_1") (pintype "passive"))
      (node (ref "C20") (pin "1") (pinfunction "1_1") (pintype "passive"))
      (node (ref "C21") (pin "1") (pinfunction "1_1") (pintype "passive"))
      (node (ref "C22") (pin "1") (pinfunction "1_1") (pintype "passive"))
      (node (ref "C23") (pin "1") (pinfunction "1_1") (pintype "passive"))
      (node (ref "C24") (pin "1") (pinfunction "1_1") (pintype "passive"))
      (node (ref "C25") (pin "1") (pinfunction "1_1") (pintype "passive"))
      (node (ref "C28") (pin "1") (pinfunction "1_1") (pintype "passive"))
      (node (ref "C29") (pin "1") (pinfunction "1_1") (pintype "passive"))
      (node (ref "C3") (pin "1") (pinfunction "1_1") (pintype "passive"))
      (node (ref "C33") (pin "2") (pinfunction "2_2") (pintype "passive"))
      (node (ref "C4") (pin "1") (pinfunction "1_1") (pintype "passive"))
      (node (ref "C5") (pin "1") (pinfunction "1_1") (pintype "passive"))
      (node (ref "C6") (pin "1") (pinfunction "1_1") (pintype "passive"))
      (node (ref "C7") (pin "2") (pinfunction "2_2") (pintype "passive"))
      (node (ref "C8") (pin "2") (pinfunction "2_2") (pintype "passive"))
      (node (ref "C9") (pin "2") (pinfunction "2_2") (pintype "passive"))
      (node (ref "DBG1") (pin "1") (pinfunction "1_1") (pintype "passive"))
      (node (ref "DBG1") (pin "11") (pinfunction "11_11") (pintype "passive"))
      (node (ref "DBG1") (pin "12") (pinfunction "12_12") (pintype "passive"))
      (node (ref "DBG1") (pin "2") (pinfunction "2_2") (pintype "passive"))
      (node (ref "DBG1") (pin "21") (pinfunction "21_21") (pintype "passive"))
      (node (ref "DBG1") (pin "22") (pinfunction "22_22") (pintype "passive"))
      (node (ref "DBG1") (pin "31") (pinfunction "31_31") (pintype "passive"))
      (node (ref "DBG1") (pin "32") (pinfunction "32_32") (pintype "passive"))
      (node (ref "N5") (pin "4") (pinfunction "4_4") (pintype "power_in"))
      (node (ref "N6") (pin "6") (pinfunction "6_6") (pintype "power_in"))
      (node (ref "N6") (pin "7") (pinfunction "7_7") (pintype "power_in"))
      (node (ref "R13") (pin "1") (pinfunction "1_1") (pintype "passive"))
      (node (ref "R14") (pin "1") (pinfunction "1_1") (pintype "passive"))
      (node (ref "R15") (pin "1") (pinfunction "1_1") (pintype "passive"))
      (node (ref "R16") (pin "2") (pinfunction "2_2") (pintype "passive"))
      (node (ref "R17") (pin "2") (pinfunction "2_2") (pintype "passive"))
      (node (ref "R18") (pin "2") (pinfunction "2_2") (pintype "passive"))
      (node (ref "R19") (pin "2") (pinfunction "2_2") (pintype "passive"))
      (node (ref "R20") (pin "2") (pinfunction "2_2") (pintype "passive"))
      (node (ref "R21") (pin "2") (pinfunction "2_2") (pintype "passive"))
      (node (ref "R23") (pin "2") (pinfunction "2_2") (pintype "passive"))
      (node (ref "R24") (pin "2") (pinfunction "2_2") (pintype "passive"))
      (node (ref "R25") (pin "2") (pinfunction "2_2") (pintype "passive"))
      (node (ref "R30") (pin "2") (pinfunction "2_2") (pintype "passive"))
      (node (ref "R39") (pin "1") (pinfunction "1_1") (pintype "passive"))
      (node (ref "R46") (pin "1") (pinfunction "1_1") (pintype "passive"))
      (node (ref "R47") (pin "1") (pinfunction "1_1") (pintype "passive"))
      (node (ref "R48") (pin "1") (pinfunction "1_1") (pintype "passive"))
      (node (ref "R49") (pin "1") (pinfunction "1_1") (pintype "passive"))
      (node (ref "R50") (pin "1") (pinfunction "1_1") (pintype "passive"))
      (node (ref "R51") (pin "1") (pinfunction "1_1") (pintype "passive"))
      (node (ref "TNC_PROG") (pin "3") (pinfunction "3_3") (pintype "passive"))
      (node (ref "TNC_PTT") (pin "2") (pinfunction "K_2") (pintype "passive"))
      (node (ref "U1") (pin "4") (pinfunction "GND_4") (pintype "power_in"))
      (node (ref "U2") (pin "2") (pinfunction "GND_2") (pintype "power_in"))
      (node (ref "U3") (pin "1") (pinfunction "A0_1") (pintype "input"))
      (node (ref "U3") (pin "2") (pinfunction "A1_2") (pintype "input"))
      (node (ref "U3") (pin "3") (pinfunction "A2_3") (pintype "input"))
      (node (ref "U3") (pin "8") (pinfunction "GND_8") (pintype "power_in"))
      (node (ref "U4") (pin "3") (pinfunction "GND_3") (pintype "power_in"))
      (node (ref "U4") (pin "7") (pinfunction "AD1_7") (pintype "input"))
      (node (ref "U4") (pin "8") (pinfunction "AD0_8") (pintype "input"))
      (node (ref "U5") (pin "12") (pinfunction "VSS_12") (pintype "power_in"))
      (node (ref "U5") (pin "14") (pinfunction "RXEQ_14") (pintype "input"))
      (node (ref "U6") (pin "5") (pinfunction "VSS_5") (pintype "power_in"))
      (node (ref "U6") (pin "6") (pinfunction "VSS_6") (pintype "power_in"))
      (node (ref "U7") (pin "4") (pinfunction "VSS_4") (pintype "power_in"))
      (node (ref "U7") (pin "8") (pinfunction "~{CS}_8") (pintype "input"))
      (node (ref "U8") (pin "4") (pinfunction "VSS_4") (pintype "power_in"))
      (node (ref "U9") (pin "1") (pinfunction "VSS_1") (pintype "power_in"))
      (node (ref "U9") (pin "28") (pinfunction "A0_28") (pintype "input"))
      (node (ref "U9") (pin "29") (pinfunction "A1_29") (pintype "input"))
      (node (ref "U9") (pin "30") (pinfunction "A2_30") (pintype "input"))
      (node (ref "U9") (pin "32") (pinfunction "GND_32") (pintype "power_in"))
      (node (ref "U9") (pin "33") (pinfunction "EP_33") (pintype "power_in"))
      (node (ref "UHFC") (pin "10") (pinfunction "10_10") (pintype "power_in"))
      (node (ref "UHFC") (pin "12") (pinfunction "12_12") (pintype "power_in"))
      (node (ref "USB1") (pin "4") (pinfunction "GND_4") (pintype "passive"))
      (node (ref "USB1") (pin "5") (pinfunction "SHLD1_5") (pintype "passive"))
      (node (ref "USB1") (pin "6") (pinfunction "SHLD2_6") (pintype "passive"))
      (node (ref "VHFC") (pin "1") (pinfunction "1_1") (pintype "power_in"))
      (node (ref "VHFC") (pin "10") (pinfunction "10_10") (pintype "power_in"))
      (node (ref "VHFC") (pin "8") (pinfunction "8_8") (pintype "input"))
      (node (ref "Y1") (pin "2") (pinfunction "GND_2") (pintype "power_in"))
      (node (ref "Y1") (pin "4") (pinfunction "GND_4") (pintype "power_in"))
      (node (ref "Y2") (pin "2") (pinfunction "2_2") (pintype "passive"))
    )
    (net (code "68") (name "Net-(C2-Pad2)") (class "Default")
      (node (ref "C2") (pin "2") (pinfunction "2_2") (pintype "passive"))
      (node (ref "R2") (pin "1") (pinfunction "1_1") (pintype "passive"))
      (node (ref "R3") (pin "2") (pinfunction "2_2") (pintype "passive"))
      (node (ref "R4") (pin "1") (pinfunction "1_1") (pintype "passive"))
    )
    (net (code "69") (name "Net-(C3-Pad2)") (class "Default")
      (node (ref "C3") (pin "2") (pinfunction "2_2") (pintype "passive"))
      (node (ref "R1") (pin "1") (pinfunction "1_1") (pintype "passive"))
      (node (ref "R5") (pin "2") (pinfunction "2_2") (pintype "passive"))
      (node (ref "R6") (pin "1") (pinfunction "1_1") (pintype "passive"))
    )
    (net (code "70") (name "Net-(C4-Pad2)") (class "Default")
      (node (ref "C4") (pin "2") (pinfunction "2_2") (pintype "passive"))
      (node (ref "R13") (pin "2") (pinfunction "2_2") (pintype "passive"))
      (node (ref "R7") (pin "2") (pinfunction "2_2") (pintype "passive"))
      (node (ref "R8") (pin "1") (pinfunction "1_1") (pintype "passive"))
    )
    (net (code "71") (name "Net-(C5-Pad2)") (class "Default")
      (node (ref "C5") (pin "2") (pinfunction "2_2") (pintype "passive"))
      (node (ref "R10") (pin "1") (pinfunction "1_1") (pintype "passive"))
      (node (ref "R14") (pin "2") (pinfunction "2_2") (pintype "passive"))
      (node (ref "R9") (pin "2") (pinfunction "2_2") (pintype "passive"))
    )
    (net (code "72") (name "Net-(C6-Pad2)") (class "Default")
      (node (ref "C6") (pin "2") (pinfunction "2_2") (pintype "passive"))
      (node (ref "R11") (pin "2") (pinfunction "2_2") (pintype "passive"))
      (node (ref "R12") (pin "1") (pinfunction "1_1") (pintype "passive"))
      (node (ref "R15") (pin "2") (pinfunction "2_2") (pintype "passive"))
    )
    (net (code "73") (name "Net-(C10-Pad1)") (class "Default")
      (node (ref "C10") (pin "1") (pinfunction "1_1") (pintype "passive"))
      (node (ref "R32") (pin "2") (pinfunction "2_2") (pintype "passive"))
    )
    (net (code "74") (name "Net-(C11-Pad2)") (class "Default")
      (node (ref "C11") (pin "2") (pinfunction "2_2") (pintype "passive"))
      (node (ref "C14") (pin "1") (pinfunction "1_1") (pintype "passive"))
      (node (ref "R35") (pin "1") (pinfunction "1_1") (pintype "passive"))
      (node (ref "R38") (pin "2") (pinfunction "2_2") (pintype "passive"))
    )
    (net (code "75") (name "Net-(C15-Pad1)") (class "Default")
      (node (ref "C15") (pin "1") (pinfunction "1_1") (pintype "passive"))
      (node (ref "R37") (pin "1") (pinfunction "1_1") (pintype "passive"))
      (node (ref "R39") (pin "2") (pinfunction "2_2") (pintype "passive"))
    )
    (net (code "76") (name "Net-(DS4-K)") (class "Default")
      (node (ref "DS4") (pin "2") (pinfunction "K_2") (pintype "passive"))
      (node (ref "R25") (pin "1") (pinfunction "1_1") (pintype "passive"))
    )
    (net (code "77") (name "Net-(DS5-K)") (class "Default")
      (node (ref "DS5") (pin "2") (pinfunction "K_2") (pintype "passive"))
      (node (ref "R17") (pin "1") (pinfunction "1_1") (pintype "passive"))
    )
    (net (code "78") (name "Net-(DS6-K)") (class "Default")
      (node (ref "DS6") (pin "2") (pinfunction "K_2") (pintype "passive"))
      (node (ref "R20") (pin "1") (pinfunction "1_1") (pintype "passive"))
    )
    (net (code "79") (name "Net-(DS7-K)") (class "Default")
      (node (ref "DS7") (pin "2") (pinfunction "K_2") (pintype "passive"))
      (node (ref "R24") (pin "1") (pinfunction "1_1") (pintype "passive"))
    )
    (net (code "80") (name "Net-(R35-Pad2)") (class "Default")
      (node (ref "R35") (pin "2") (pinfunction "2_2") (pintype "passive"))
      (node (ref "R36") (pin "2") (pinfunction "2_2") (pintype "passive"))
    )
    (net (code "81") (name "Net-(TACT-K)") (class "Default")
      (node (ref "R23") (pin "1") (pinfunction "1_1") (pintype "passive"))
      (node (ref "TACT") (pin "2") (pinfunction "K_2") (pintype "passive"))
    )
    (net (code "82") (name "Net-(TNC_EGY-K)") (class "Default")
      (node (ref "R34") (pin "1") (pinfunction "1_1") (pintype "passive"))
      (node (ref "TNC_EGY") (pin "2") (pinfunction "K_2") (pintype "passive"))
    )
    (net (code "83") (name "Net-(TNC_PTT-A)") (class "Default")
      (node (ref "R28") (pin "2") (pinfunction "2_2") (pintype "passive"))
      (node (ref "TNC_PTT") (pin "1") (pinfunction "A_1") (pintype "passive"))
    )
    (net (code "84") (name "Net-(U2A-1Y)") (class "Default")
      (node (ref "U2") (pin "6") (pinfunction "1Y_6") (pintype "output"))
      (node (ref "UHF") (pin "1") (pinfunction "A_1") (pintype "passive"))
    )
    (net (code "85") (name "Net-(U2B-2Y)") (class "Default")
      (node (ref "U2") (pin "4") (pinfunction "2Y_4") (pintype "output"))
      (node (ref "VHF") (pin "1") (pinfunction "A_1") (pintype "passive"))
    )
    (net (code "86") (name "Net-(U5-RDY)") (class "Default")
      (node (ref "R26") (pin "1") (pinfunction "1_1") (pintype "passive"))
      (node (ref "U5") (pin "23") (pinfunction "RDY_23") (pintype "output"))
    )
    (net (code "87") (name "Net-(U5-RXAMPOUT)") (class "Default")
      (node (ref "C12") (pin "2") (pinfunction "2_2") (pintype "passive"))
      (node (ref "R33") (pin "2") (pinfunction "2_2") (pintype "passive"))
      (node (ref "U5") (pin "8") (pinfunction "RXAMPOUT_8") (pintype "output"))
    )
    (net (code "88") (name "Net-(U5-RXIN)") (class "Default")
      (node (ref "C12") (pin "1") (pinfunction "1_1") (pintype "passive"))
      (node (ref "R32") (pin "1") (pinfunction "1_1") (pintype "passive"))
      (node (ref "R33") (pin "1") (pinfunction "1_1") (pintype "passive"))
      (node (ref "U5") (pin "7") (pinfunction "RXIN_7") (pintype "input"))
    )
    (net (code "89") (name "Net-(U5-TXOUT)") (class "Default")
      (node (ref "R37") (pin "2") (pinfunction "2_2") (pintype "passive"))
      (node (ref "U5") (pin "11") (pinfunction "TXOUT_11") (pintype "output"))
    )
    (net (code "90") (name "Net-(U5-VBias)") (class "Default")
      (node (ref "C13") (pin "1") (pinfunction "1_1") (pintype "passive"))
      (node (ref "U5") (pin "13") (pinfunction "VBias_13") (pintype "power_in"))
    )
    (net (code "91") (name "Net-(U6-RA1)") (class "Default")
      (node (ref "R27") (pin "2") (pinfunction "2_2") (pintype "passive"))
      (node (ref "R30") (pin "1") (pinfunction "1_1") (pintype "passive"))
      (node (ref "U6") (pin "20") (pinfunction "RA1_20") (pintype "bidirectional"))
    )
    (net (code "92") (name "Net-(U7-VIN+)") (class "Default")
      (node (ref "R36") (pin "1") (pinfunction "1_1") (pintype "passive"))
      (node (ref "U7") (pin "3") (pinfunction "VIN+_3") (pintype "input"))
    )
    (net (code "93") (name "Net-(U7-VIN-)") (class "Default")
      (node (ref "C10") (pin "2") (pinfunction "2_2") (pintype "passive"))
      (node (ref "C11") (pin "1") (pinfunction "1_1") (pintype "passive"))
      (node (ref "U7") (pin "2") (pinfunction "VIN-_2") (pintype "input"))
      (node (ref "U7") (pin "6") (pinfunction "VOUT_6") (pintype "output"))
    )
    (net (code "94") (name "Net-(U7-VREF)") (class "Default")
      (node (ref "C16") (pin "2") (pinfunction "2_2") (pintype "passive"))
      (node (ref "R38") (pin "1") (pinfunction "1_1") (pintype "passive"))
      (node (ref "U7") (pin "5") (pinfunction "VREF_5") (pintype "power_in"))
    )
    (net (code "95") (name "Net-(UACT-K)") (class "Default")
      (node (ref "R16") (pin "1") (pinfunction "1_1") (pintype "passive"))
      (node (ref "UACT") (pin "2") (pinfunction "K_2") (pintype "passive"))
    )
    (net (code "96") (name "Net-(UHF-K)") (class "Default")
      (node (ref "R18") (pin "1") (pinfunction "1_1") (pintype "passive"))
      (node (ref "UHF") (pin "2") (pinfunction "K_2") (pintype "passive"))
    )
    (net (code "97") (name "Net-(VACT-K)") (class "Default")
      (node (ref "R19") (pin "1") (pinfunction "1_1") (pintype "passive"))
      (node (ref "VACT") (pin "2") (pinfunction "K_2") (pintype "passive"))
    )
    (net (code "98") (name "Net-(VHF-K)") (class "Default")
      (node (ref "R21") (pin "1") (pinfunction "1_1") (pintype "passive"))
      (node (ref "VHF") (pin "2") (pinfunction "K_2") (pintype "passive"))
    )
    (net (code "99") (name "PA_PWR") (class "Default")
      (node (ref "D1") (pin "1") (pinfunction "K_1") (pintype "passive"))
      (node (ref "PA_Power") (pin "1") (pinfunction "1_1") (pintype "passive"))
      (node (ref "UHFC") (pin "1") (pinfunction "1_1") (pintype "power_in"))
      (node (ref "VHFC") (pin "18") (pinfunction "18_18") (pintype "output"))
    )
    (net (code "100") (name "USB_Vbus") (class "Default")
      (node (ref "C28") (pin "2") (pinfunction "2_2") (pintype "passive"))
      (node (ref "C29") (pin "2") (pinfunction "2_2") (pintype "passive"))
      (node (ref "FB1") (pin "1") (pinfunction "1_1") (pintype "passive"))
      (node (ref "USB1") (pin "1") (pinfunction "VBUS_1") (pintype "passive"))
      (node (ref "Vbus") (pin "1") (pinfunction "1_1") (pintype "passive"))
    )
    (net (code "101") (name "Vbus_Filtered") (class "Default")
      (node (ref "D1") (pin "2") (pinfunction "A_2") (pintype "passive"))
      (node (ref "FB1") (pin "2") (pinfunction "2_2") (pintype "passive"))
      (node (ref "Vbus_f") (pin "1") (pinfunction "1_1") (pintype "passive"))
    )
    (net (code "102") (name "unconnected-(N5-Pad5)") (class "Default")
      (node (ref "N5") (pin "5") (pinfunction "5_5") (pintype "passive+no_connect"))
    )
    (net (code "103") (name "unconnected-(N6-Pad1)") (class "Default")
      (node (ref "N6") (pin "1") (pinfunction "1_1") (pintype "passive+no_connect"))
    )
    (net (code "104") (name "unconnected-(N6-Pad2)") (class "Default")
      (node (ref "N6") (pin "2") (pinfunction "2_2") (pintype "passive+no_connect"))
    )
    (net (code "105") (name "unconnected-(N6-Pad3)") (class "Default")
      (node (ref "N6") (pin "3") (pinfunction "3_3") (pintype "passive+no_connect"))
    )
    (net (code "106") (name "unconnected-(N6-Pad8)") (class "Default")
      (node (ref "N6") (pin "8") (pinfunction "8_8") (pintype "passive+no_connect"))
    )
    (net (code "107") (name "unconnected-(N9-Pad7)") (class "Default")
      (node (ref "N9") (pin "7") (pinfunction "7_7") (pintype "passive+no_connect"))
    )
    (net (code "108") (name "unconnected-(N9-Pad8)") (class "Default")
      (node (ref "N9") (pin "8") (pinfunction "8_8") (pintype "passive+no_connect"))
    )
    (net (code "109") (name "unconnected-(U3-~{INT}-Pad13)") (class "Default")
      (node (ref "U3") (pin "13") (pinfunction "~{INT}_13") (pintype "open_collector+no_connect"))
    )
    (net (code "110") (name "unconnected-(U4-~{PCTLZ}-Pad6)") (class "Default")
      (node (ref "U4") (pin "6") (pinfunction "~{PCTLZ}_6") (pintype "output+no_connect"))
    )
    (net (code "111") (name "unconnected-(U5-DET-Pad20)") (class "Default")
      (node (ref "U5") (pin "20") (pinfunction "DET_20") (pintype "output+no_connect"))
    )
    (net (code "112") (name "unconnected-(U5-NC-Pad3)") (class "Default")
      (node (ref "U5") (pin "3") (pinfunction "NC_3") (pintype "passive+no_connect"))
    )
    (net (code "113") (name "unconnected-(U5-NC-Pad4)") (class "Default")
      (node (ref "U5") (pin "4") (pinfunction "NC_4") (pintype "passive+no_connect"))
    )
    (net (code "114") (name "unconnected-(U5-NC-Pad9)") (class "Default")
      (node (ref "U5") (pin "9") (pinfunction "NC_9") (pintype "passive+no_connect"))
    )
    (net (code "115") (name "unconnected-(U5-NC-Pad10)") (class "Default")
      (node (ref "U5") (pin "10") (pinfunction "NC_10") (pintype "passive+no_connect"))
    )
    (net (code "116") (name "unconnected-(U5-NC-Pad15)") (class "Default")
      (node (ref "U5") (pin "15") (pinfunction "NC_15") (pintype "passive+no_connect"))
    )
    (net (code "117") (name "unconnected-(U5-NC-Pad16)") (class "Default")
      (node (ref "U5") (pin "16") (pinfunction "NC_16") (pintype "passive+no_connect"))
    )
    (net (code "118") (name "unconnected-(U5-NC-Pad21)") (class "Default")
      (node (ref "U5") (pin "21") (pinfunction "NC_21") (pintype "passive+no_connect"))
    )
    (net (code "119") (name "unconnected-(U5-NC-Pad22)") (class "Default")
      (node (ref "U5") (pin "22") (pinfunction "NC_22") (pintype "passive+no_connect"))
    )
    (net (code "120") (name "unconnected-(U6-RB1-Pad8)") (class "Default")
      (node (ref "U6") (pin "8") (pinfunction "RB1_8") (pintype "bidirectional+no_connect"))
    )
    (net (code "121") (name "unconnected-(U6-RB4-Pad11)") (class "Default")
      (node (ref "U6") (pin "11") (pinfunction "RB4_11") (pintype "bidirectional+no_connect"))
    )
    (net (code "122") (name "unconnected-(U7-NC-Pad1)") (class "Default")
      (node (ref "U7") (pin "1") (pinfunction "NC_1") (pintype "passive+no_connect"))
    )
    (net (code "123") (name "unconnected-(U8-NC-Pad3)") (class "Default")
      (node (ref "U8") (pin "3") (pinfunction "NC_3") (pintype "passive+no_connect"))
    )
    (net (code "124") (name "unconnected-(U9-NC-Pad2)") (class "Default")
      (node (ref "U9") (pin "2") (pinfunction "NC_2") (pintype "passive+no_connect"))
    )
    (net (code "125") (name "unconnected-(U9-NC-Pad19)") (class "Default")
      (node (ref "U9") (pin "19") (pinfunction "NC_19") (pintype "passive+no_connect"))
    )
    (net (code "126") (name "unconnected-(U9-NC-Pad20)") (class "Default")
      (node (ref "U9") (pin "20") (pinfunction "NC_20") (pintype "passive+no_connect"))
    )
    (net (code "127") (name "unconnected-(U9-NC-Pad21)") (class "Default")
      (node (ref "U9") (pin "21") (pinfunction "NC_21") (pintype "passive+no_connect"))
    )
    (net (code "128") (name "unconnected-(U9-NC-Pad22)") (class "Default")
      (node (ref "U9") (pin "22") (pinfunction "NC_22") (pintype "passive+no_connect"))
    )
    (net (code "129") (name "unconnected-(U9-NC-Pad23)") (class "Default")
      (node (ref "U9") (pin "23") (pinfunction "NC_23") (pintype "passive+no_connect"))
    )
    (net (code "130") (name "unconnected-(U9-X4-Pad7)") (class "Default")
      (node (ref "U9") (pin "7") (pinfunction "X4_7") (pintype "passive+no_connect"))
    )
    (net (code "131") (name "unconnected-(U9-X5-Pad8)") (class "Default")
      (node (ref "U9") (pin "8") (pinfunction "X5_8") (pintype "passive+no_connect"))
    )
    (net (code "132") (name "unconnected-(U9-X6-Pad17)") (class "Default")
      (node (ref "U9") (pin "17") (pinfunction "X6_17") (pintype "passive+no_connect"))
    )
    (net (code "133") (name "unconnected-(U9-X7-Pad18)") (class "Default")
      (node (ref "U9") (pin "18") (pinfunction "X7_18") (pintype "passive+no_connect"))
    )
    (net (code "134") (name "unconnected-(U9-Y0-Pad9)") (class "Default")
      (node (ref "U9") (pin "9") (pinfunction "Y0_9") (pintype "passive+no_connect"))
    )
    (net (code "135") (name "unconnected-(U9-Y1-Pad10)") (class "Default")
      (node (ref "U9") (pin "10") (pinfunction "Y1_10") (pintype "passive"))
    )
    (net (code "136") (name "unconnected-(U9-Y4-Pad13)") (class "Default")
      (node (ref "U9") (pin "13") (pinfunction "Y4_13") (pintype "passive+no_connect"))
    )
    (net (code "137") (name "unconnected-(U9-Y5-Pad14)") (class "Default")
      (node (ref "U9") (pin "14") (pinfunction "Y5_14") (pintype "passive+no_connect"))
    )
    (net (code "138") (name "unconnected-(U9-Y6-Pad15)") (class "Default")
      (node (ref "U9") (pin "15") (pinfunction "Y6_15") (pintype "passive+no_connect"))
    )
    (net (code "139") (name "unconnected-(U9-Y7-Pad16)") (class "Default")
      (node (ref "U9") (pin "16") (pinfunction "Y7_16") (pintype "passive+no_connect"))
    )
  )
)
